# obd_schematic_27th_Jan_2026.net
KiCad netlist of a schematic drawn in EasyEDA Pro
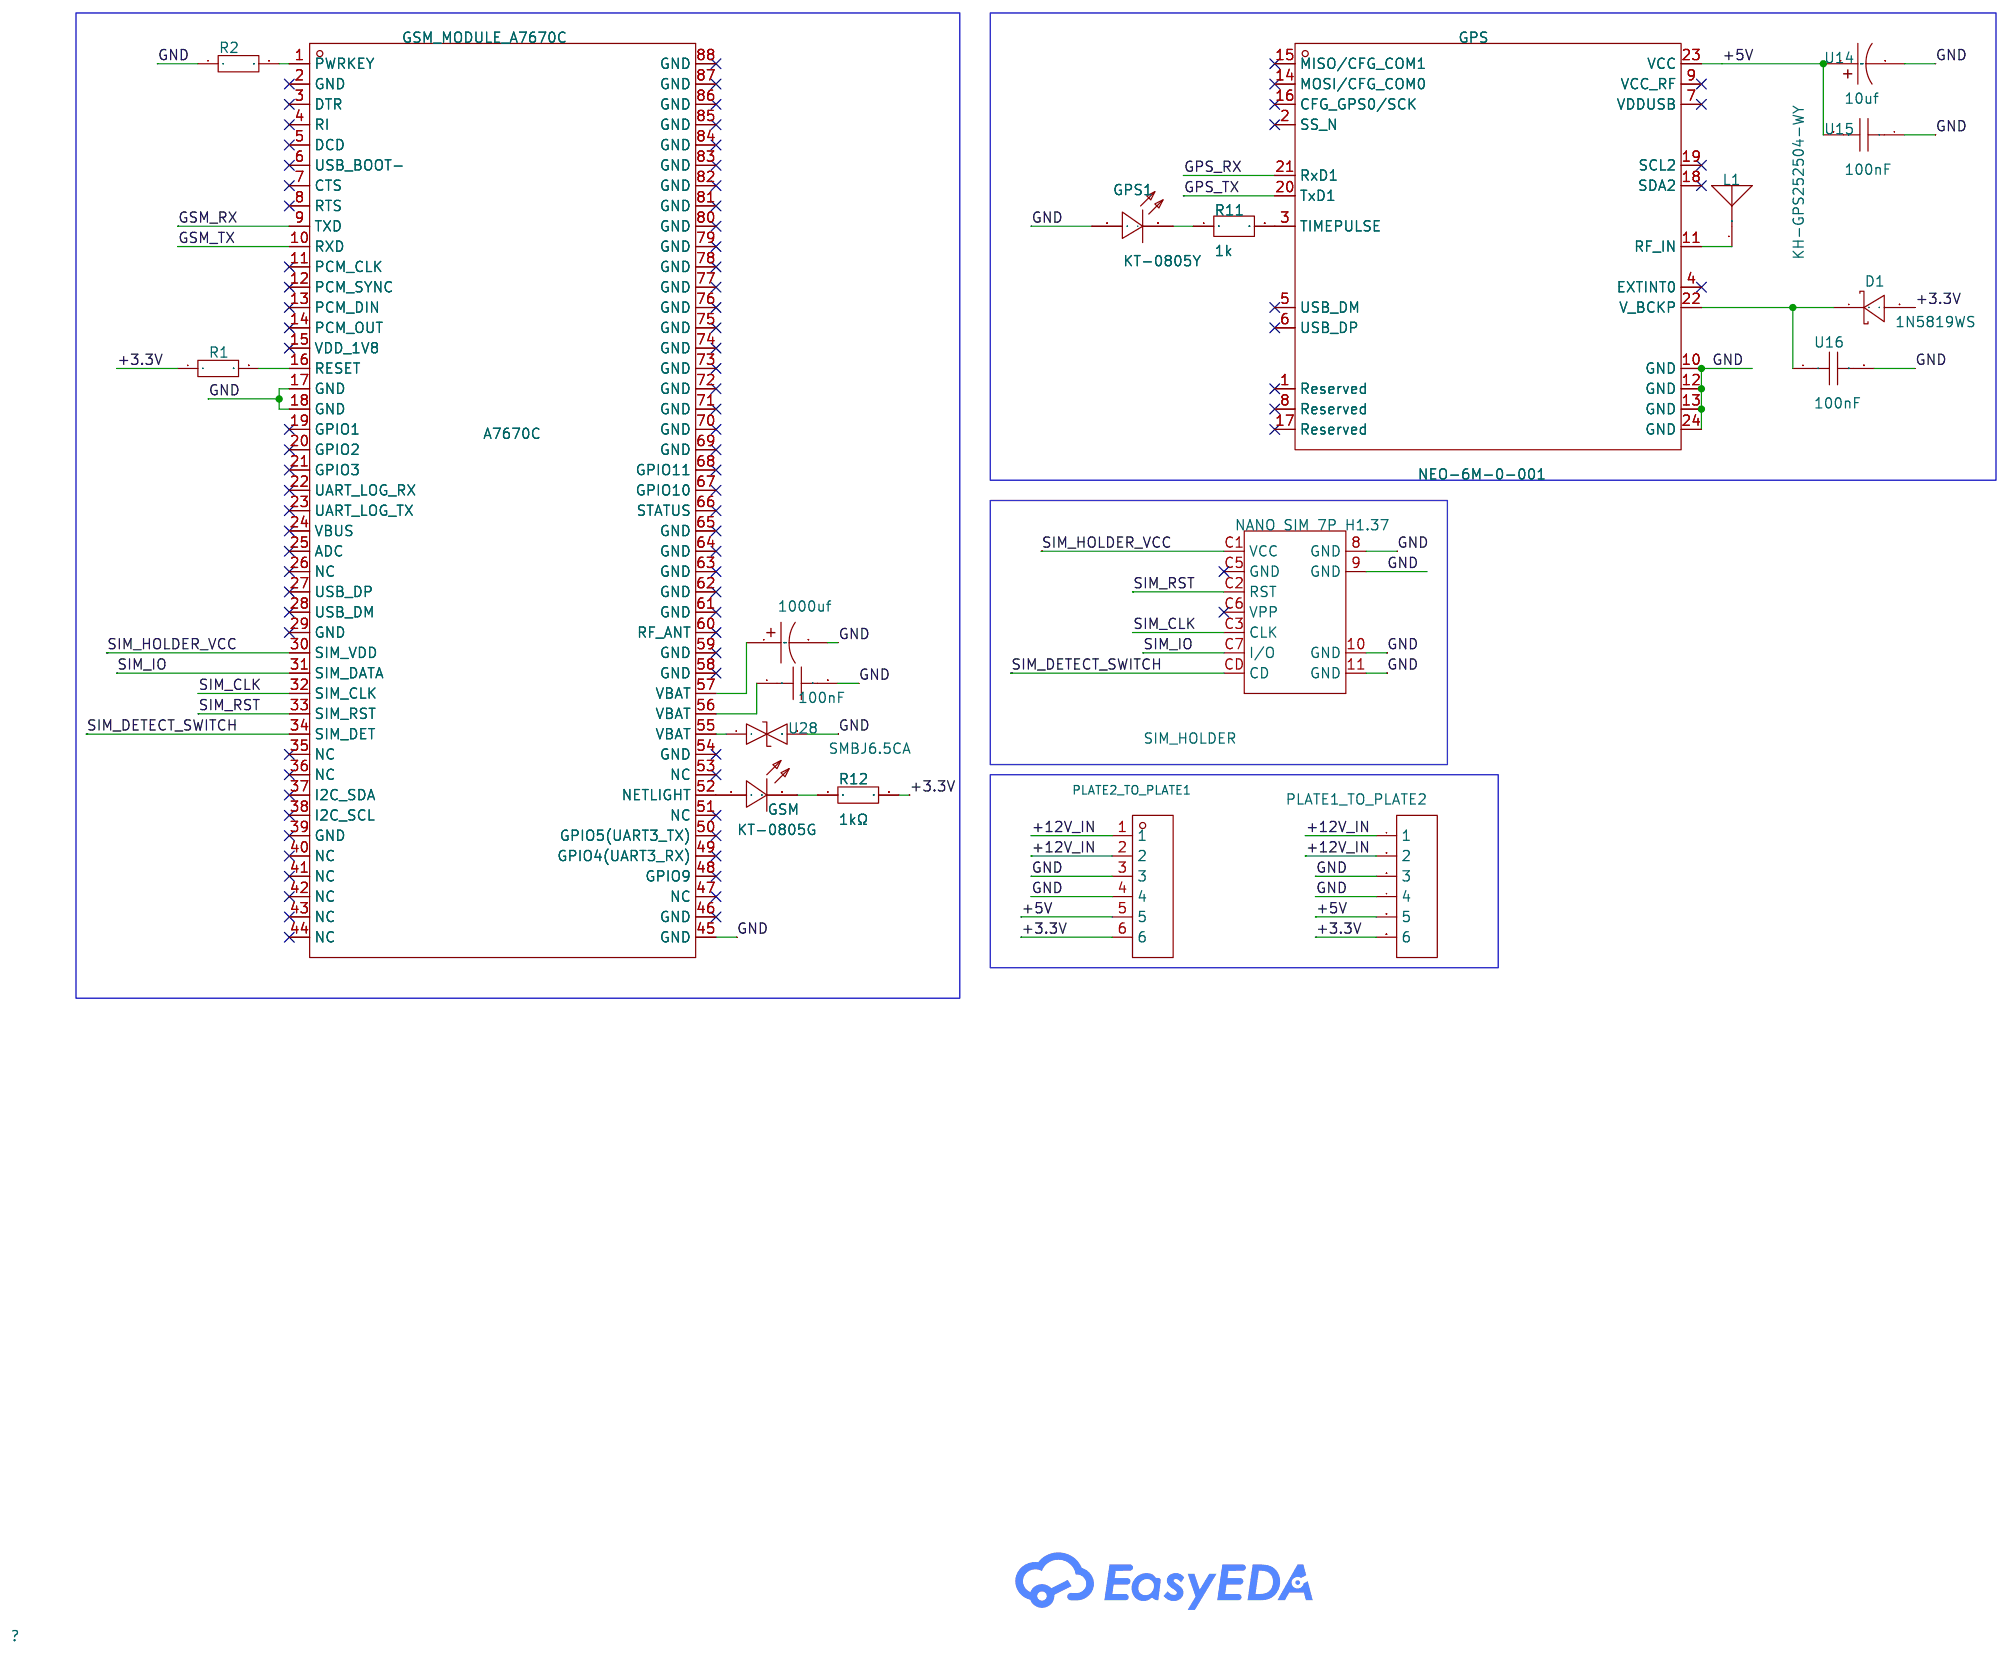
[diagram p0: gps_gsm]
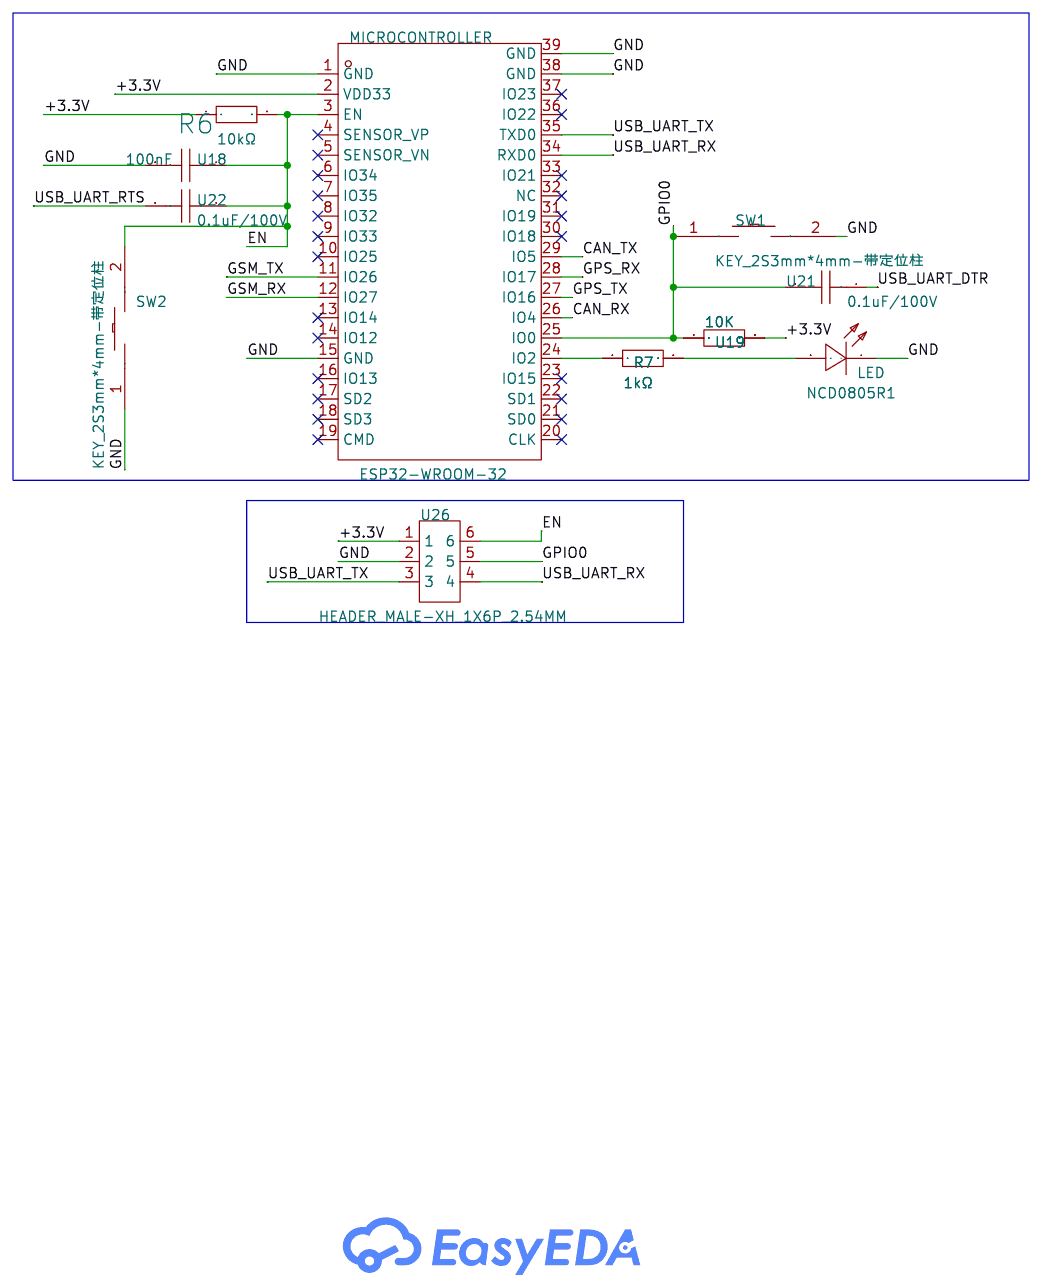
[diagram p1: Microcontroller]
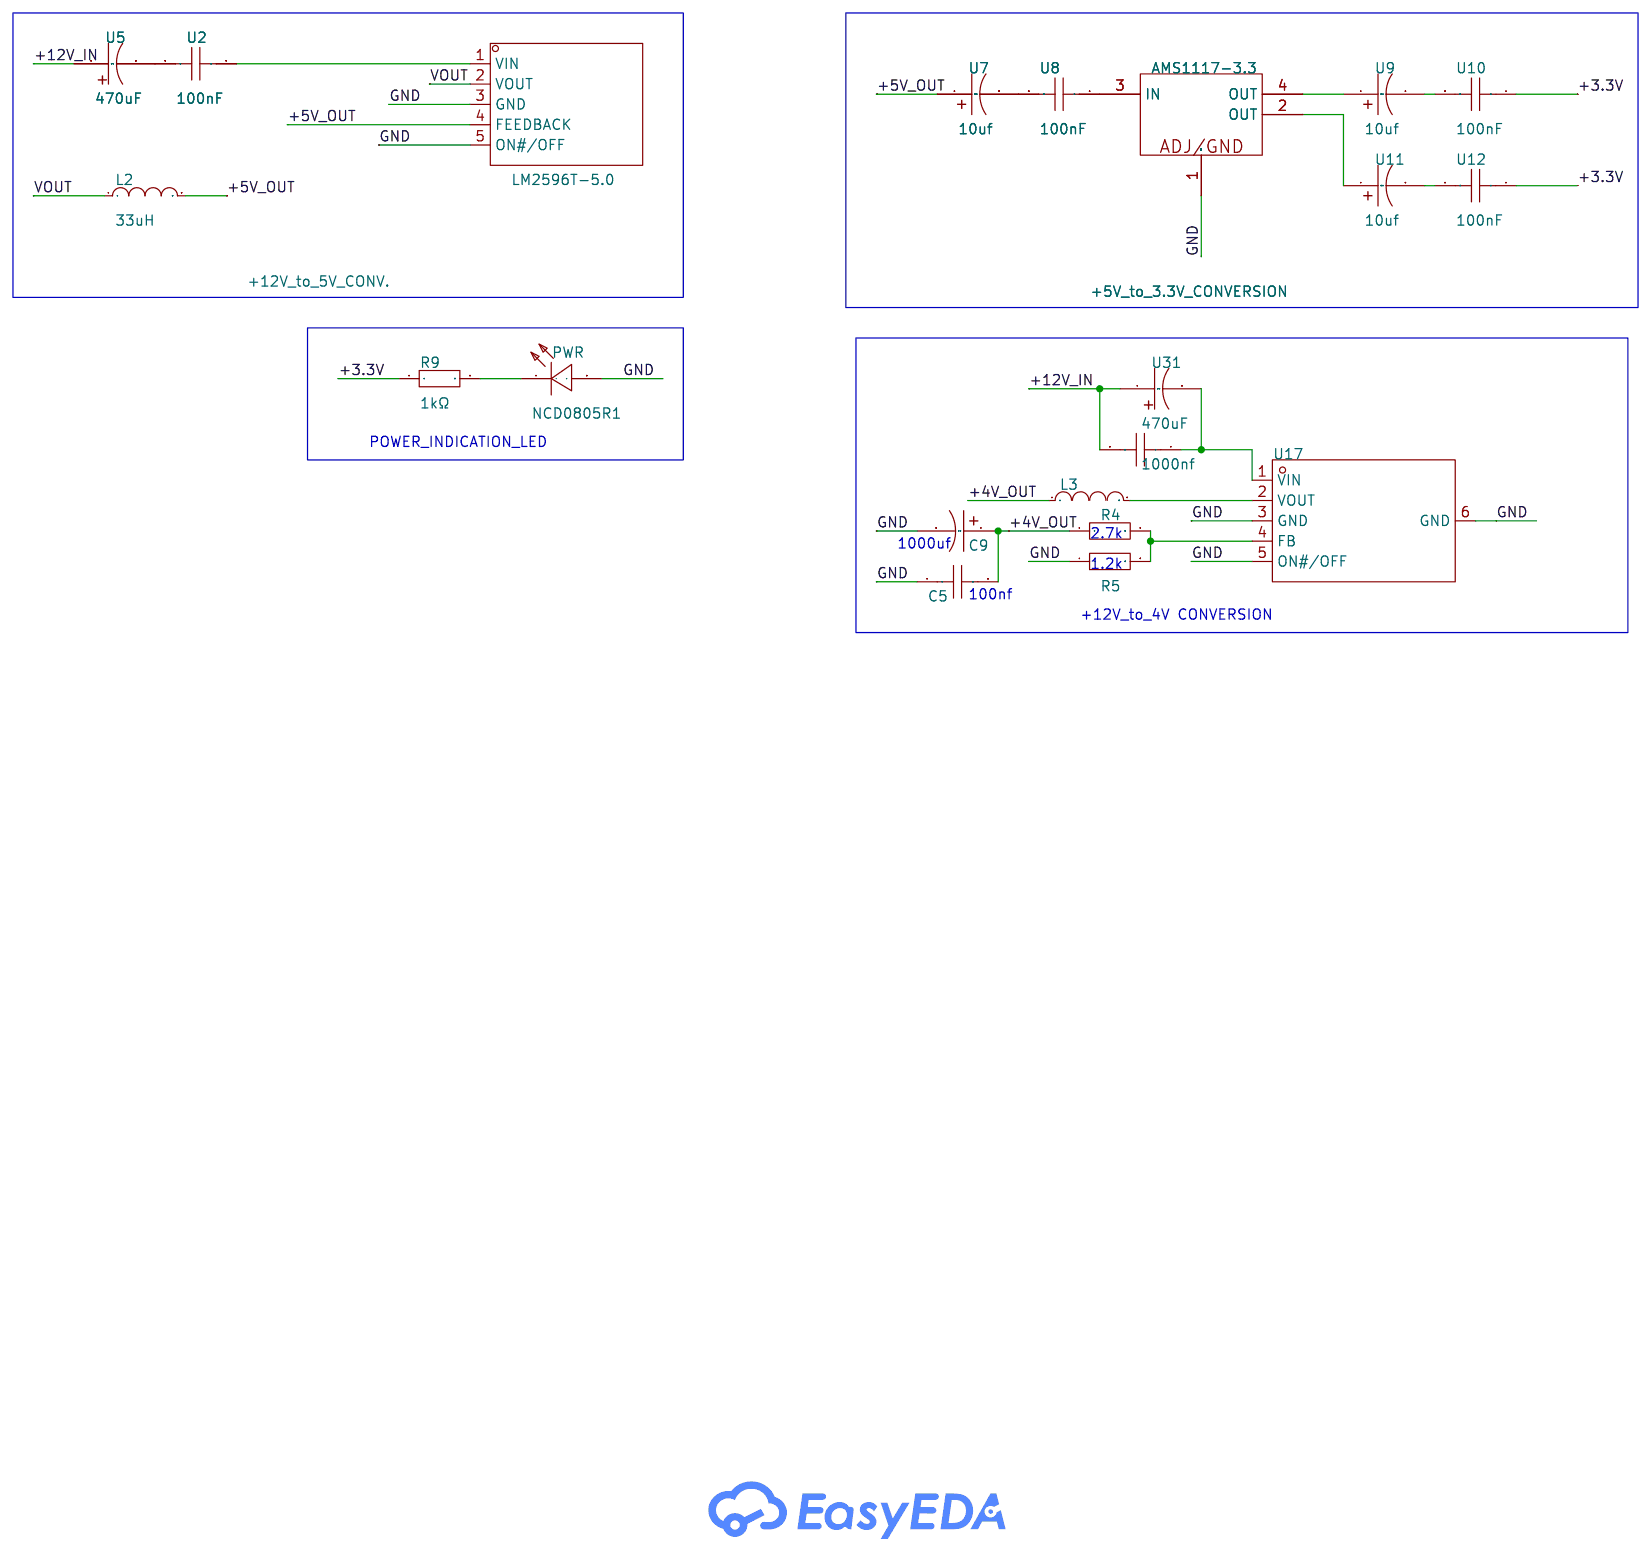
[diagram p2: power_supply]
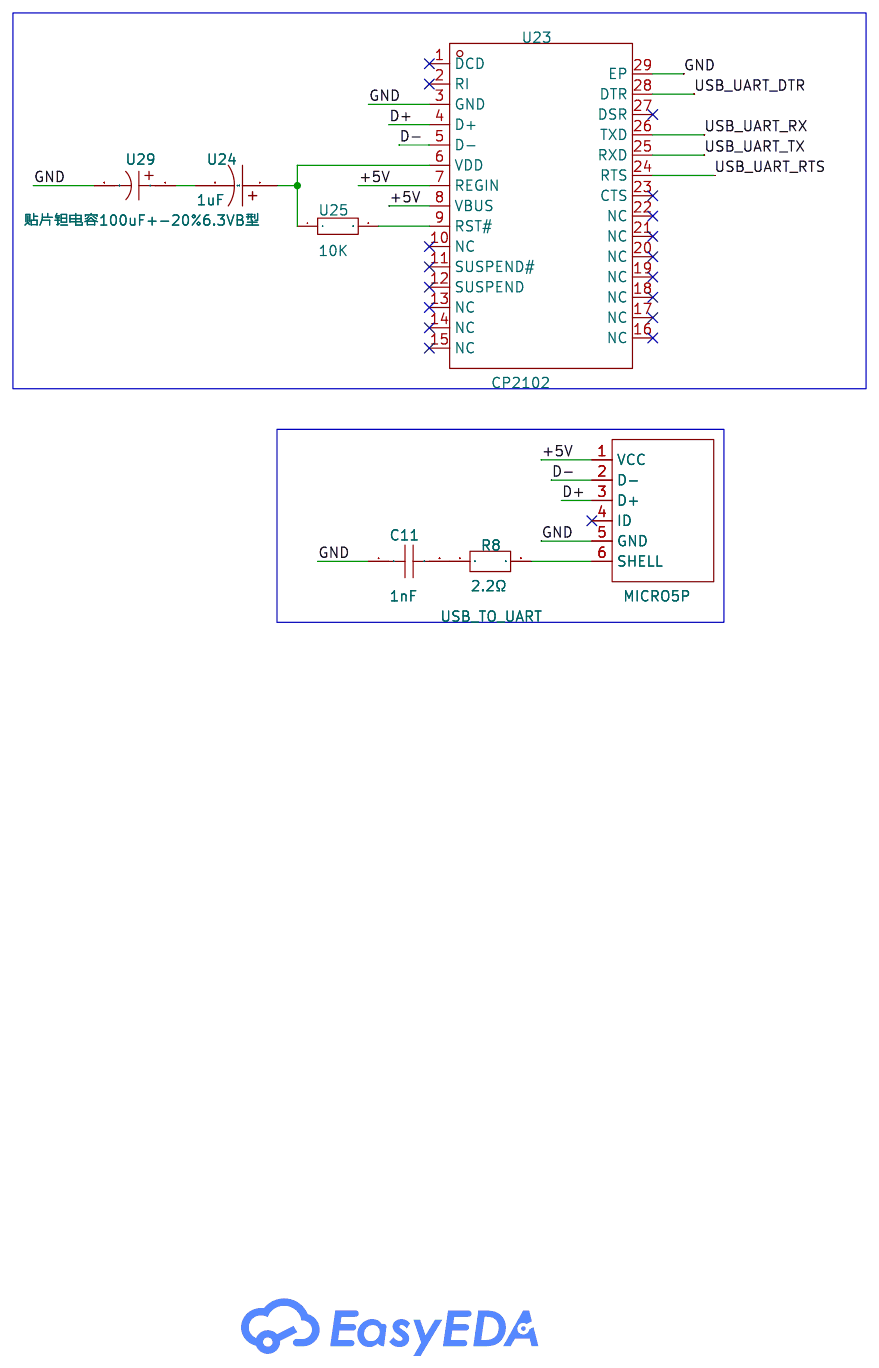
[diagram p3: usb_to_uart]
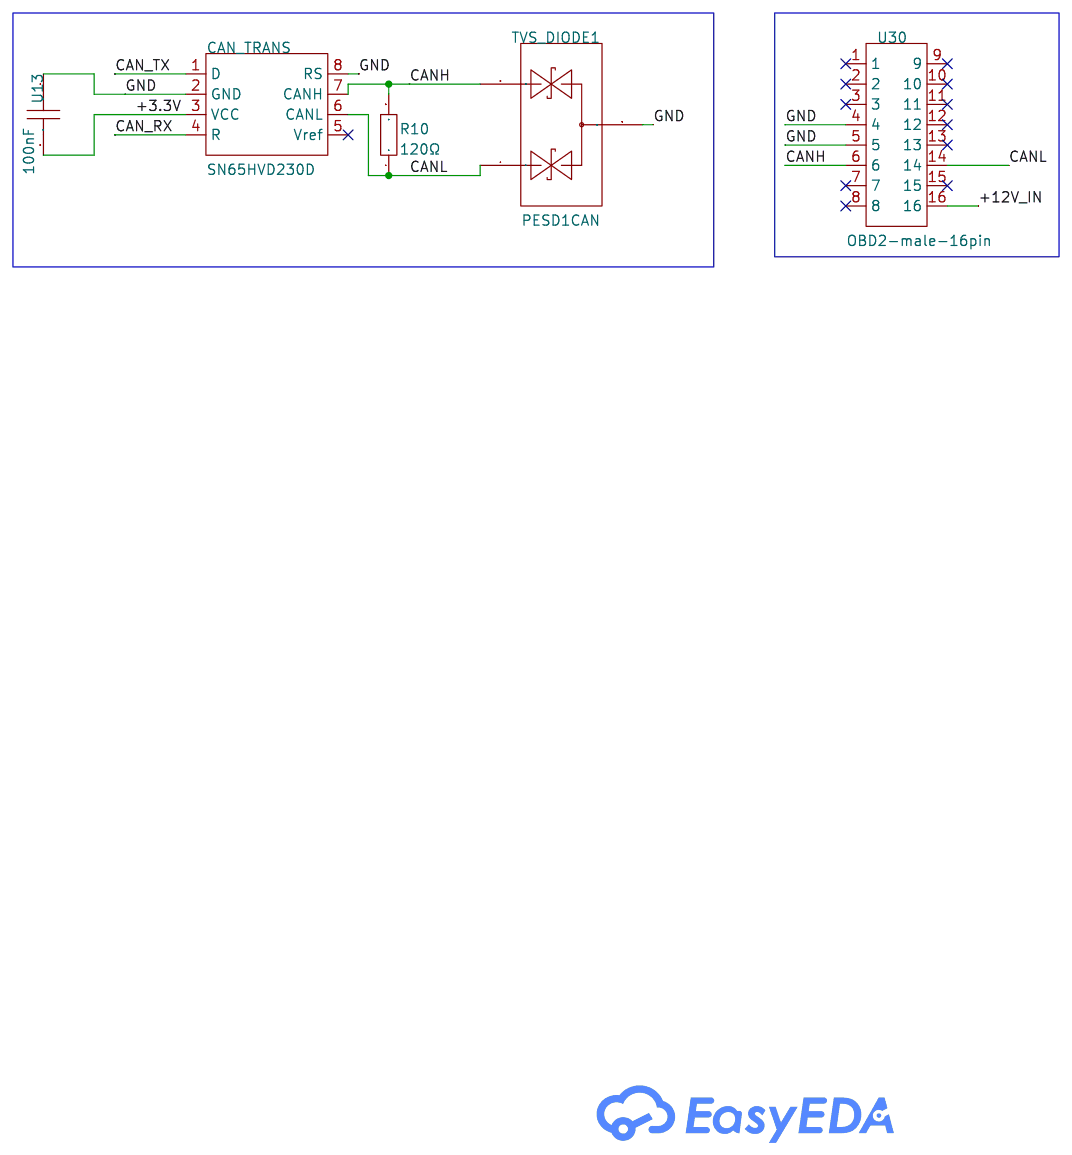
[diagram p4: can_obd_male_connector]

(export (version "E")
  (design (tool "Eeschema 10.0.6"))
  (components
    (comp (ref "100nF")
      (value "100nF")
      (footprint "easyedapro:CAP-TH_L18.0-W6.0-P15.00-D1.2")
      (fields
        (field (name "Manufacturer Part") "SMQP104K275XXD2B1515")
        (field (name "Manufacturer") "CHAMPION(全鹏)")
      )
      (libsource (lib "easyedapro") (part "SMQP104K275XXD2B1515"))
    )
    (comp (ref "1000uf")
      (value "1000uF")
      (footprint "easyedapro:CAP-TH_BD6.3-P2.50-D1.0-FD")
      (fields
        (field (name "Manufacturer Part") "SHW1000UF6.3V6.3X11")
        (field (name "Manufacturer") "KNSCHA(科尼盛)")
      )
      (libsource (lib "easyedapro") (part "SHW1000UF6.3V6.3X11"))
    )
    (comp (ref "D1")
      (value "1N5819WS")
      (footprint "easyedapro:SOD-323_L1.8-W1.3-LS2.5-RD")
      (fields (field (name "Manufacturer") "Hottech(合科泰)"))
      (libsource (lib "easyedapro") (part "1N5819WS"))
    )
    (comp (ref "GPS")
      (value "NEO-6M-0-001")
      (footprint "easyedapro:GPSM-SMD_24P-L16.0-W12.2-P1.10")
      (libsource (lib "easyedapro") (part "NEO-6M-0-001"))
    )
    (comp (ref "GPS1")
      (value "KT-0805Y")
      (footprint "easyedapro:LED0805-R-RD")
      (fields (field (name "Manufacturer") "KENTO"))
      (libsource (lib "easyedapro") (part "17-21SUYC/TR8"))
    )
    (comp (ref "GSM")
      (value "KT-0805G")
      (footprint "easyedapro:LED0805-R-RD")
      (fields (field (name "Manufacturer") "KENTO"))
      (libsource (lib "easyedapro") (part "0805G (Green)"))
    )
    (comp (ref "GSM_MODULE_A7670C")
      (value "A7670C")
      (footprint "easyedapro:WIRELM-SMD-88_L24.0-W24.0-P1.00-BL")
      (libsource (lib "easyedapro") (part "A7670C"))
    )
    (comp (ref "L1")
      (value "KH-GPS252504-WY")
      (footprint "easyedapro:ANT-TH_KH-GPS252504-WY")
      (fields (field (name "Manufacturer") "kinghelm(金航标)"))
      (libsource (lib "easyedapro") (part "KH-GPS252504-WY"))
    )
    (comp (ref "PLATE1_TO_PLATE2")
      (value "~")
      (footprint "easyedapro:HDR-TH_6P-P2.54-V-M-1")
      (libsource (lib "easyedapro") (part "Header-Male-2.54_1x6"))
    )
    (comp (ref "PLATE2_TO_PLATE1")
      (value "~")
      (footprint "easyedapro:HDR-TH_6P-P2.54-V-F")
      (libsource (lib "easyedapro") (part "Header-Female-2.54_1x6"))
    )
    (comp (ref "R1")
      (value "10kΩ")
      (footprint "easyedapro:R0805")
      (fields
        (field (name "Manufacturer Part") "RMCF0805FT10K0")
        (field (name "Manufacturer") "SEI(Stackpole Electronics Inc.)")
      )
      (libsource (lib "easyedapro") (part "RMCF0805FT10K0"))
    )
    (comp (ref "R2")
      (value "10kΩ")
      (footprint "easyedapro:R0805")
      (fields
        (field (name "Manufacturer Part") "RMCF0805FT10K0")
        (field (name "Manufacturer") "SEI(Stackpole Electronics Inc.)")
      )
      (libsource (lib "easyedapro") (part "RMCF0805FT10K0"))
    )
    (comp (ref "R11") (value "1k") (footprint "easyedapro:R0603") (libsource (lib "easyedapro") (part "1K")))
    (comp (ref "R12")
      (value "1kΩ")
      (footprint "easyedapro:R0805")
      (fields
        (field (name "Manufacturer Part") "0805W8F1001T5E")
        (field (name "Manufacturer") "UNI-ROYAL(厚声)")
      )
      (libsource (lib "easyedapro") (part "0805W8F1001T5E"))
    )
    (comp (ref "SIM_HOLDER")
      (value "NANO SIM 7P H1.37")
      (footprint "easyedapro:SIM-SMD_NANO-SIM-7P-H1.37")
      (fields (field (name "Manufacturer") "SHOU HAN(首韩)"))
      (libsource (lib "easyedapro") (part "NANO SIM 7P H1.37"))
    )
    (comp (ref "U14")
      (value "10uf")
      (footprint "easyedapro:CAP-SMD_L2.0-W1.3-FD")
      (libsource (lib "easyedapro") (part "10UF_C9900016685"))
    )
    (comp (ref "U15")
      (value "100nF")
      (footprint "easyedapro:CAP-TH_L5.0-W2.5-P5.00-D1.0")
      (libsource (lib "easyedapro") (part "100NF_C9900015256"))
    )
    (comp (ref "U16")
      (value "100nF")
      (footprint "easyedapro:CAP-TH_L5.0-W2.5-P5.00-D1.0")
      (libsource (lib "easyedapro") (part "100NF_C9900015256"))
    )
    (comp (ref "U28")
      (value "SMBJ6.5CA")
      (footprint "easyedapro:SMB_L4.6-W3.5-LS5.3-BI")
      (fields (field (name "Manufacturer") "R+O(宏嘉诚)"))
      (libsource (lib "easyedapro") (part "SMBJ6.5CA_C7420377"))
    )
    (comp (ref "LED")
      (value "NCD0805R1")
      (footprint "easyedapro:LED0805-RD")
      (fields (field (name "Manufacturer") "国星光电"))
      (libsource (lib "easyedapro") (part "FC-2012HRK-620D"))
    )
    (comp (ref "MICROCONTROLLER")
      (value "ESP32-WROOM-32")
      (footprint "easyedapro:WIFIM-SMD_39P-L25.5-W18.0-P1.27")
      (libsource (lib "easyedapro") (part "ESP32-WROOM-32_C503587"))
    )
    (comp (ref "R6")
      (value "10kΩ")
      (footprint "easyedapro:R0603")
      (fields
        (field (name "Manufacturer Part") "0603WAF1002T5E")
        (field (name "Manufacturer") "UNI-ROYAL(厚声)")
      )
      (libsource (lib "easyedapro") (part "0603WAF1002T5E"))
    )
    (comp (ref "R7")
      (value "1kΩ")
      (footprint "easyedapro:R0805")
      (fields
        (field (name "Manufacturer Part") "0805W8F1001T5E")
        (field (name "Manufacturer") "UNI-ROYAL(厚声)")
      )
      (libsource (lib "easyedapro") (part "0805W8F1001T5E"))
    )
    (comp (ref "SW1")
      (value "KEY_2S3mm*4mm-带定位柱")
      (footprint "easyedapro:KEY-SMD_L4.0-W3.7-LS4.8")
      (libsource (lib "easyedapro") (part "KEY_2S3MM*4MM-带定位柱"))
    )
    (comp (ref "SW2")
      (value "KEY_2S3mm*4mm-带定位柱")
      (footprint "easyedapro:KEY-SMD_L4.0-W3.7-LS4.8")
      (libsource (lib "easyedapro") (part "KEY_2S3MM*4MM-带定位柱"))
    )
    (comp (ref "U18")
      (value "100nF")
      (footprint "easyedapro:CAP-TH_L5.0-W2.5-P5.00-D1.0")
      (libsource (lib "easyedapro") (part "100NF_C9900015256"))
    )
    (comp (ref "U19")
      (value "10K")
      (footprint "easyedapro:R0805")
      (libsource (lib "easyedapro") (part "10K"))
    )
    (comp (ref "U21")
      (value "0.1uF/100V")
      (footprint "easyedapro:C0805")
      (libsource (lib "easyedapro") (part "0.1UF/100V"))
    )
    (comp (ref "U22")
      (value "0.1uF/100V")
      (footprint "easyedapro:C0805")
      (libsource (lib "easyedapro") (part "0.1UF/100V"))
    )
    (comp (ref "U26")
      (value "HEADER_MALE-XH_1X6P_2.54MM")
      (footprint "easyedapro:CONN-TH_6P-P2.50-V-M_HEADER-MALE")
      (libsource (lib "easyedapro") (part "HEADER_MALE-XH_1X6P_2.54MM"))
    )
    (comp (ref "+5V_to_3.3V_CONVERSION")
      (value "AMS1117-3.3")
      (footprint "easyedapro:SOT-223-3_L6.4-W3.5-P2.30-LS7.0-BR")
      (fields (field (name "Manufacturer") "国芯佳品"))
      (libsource (lib "easyedapro") (part "AMS1117-3.3_C2992570"))
    )
    (comp (ref "+12V_to_5V_CONV.")
      (value "LM2596T-5.0")
      (footprint "easyedapro:TO-220-5L_L10.2-W4.5-P1.71-L")
      (libsource (lib "easyedapro") (part "LM2596-5V"))
    )
    (comp (ref "1000nf")
      (value "100nF")
      (footprint "easyedapro:CAP-TH_L7.3-W3.2-P5.00-D0.5")
      (fields
        (field (name "Manufacturer Part") "MMTSA0050J10400000200")
        (field (name "Manufacturer") "NISSEI(日精)")
      )
      (libsource (lib "easyedapro") (part "MMTSA0050J10400000200"))
    )
    (comp (ref "C5")
      (value "100nF")
      (footprint "easyedapro:CAP-TH_L18.0-W6.0-P15.00-D1.2")
      (fields
        (field (name "Manufacturer Part") "SMQP104K275XXD2B1515")
        (field (name "Manufacturer") "CHAMPION(全鹏)")
      )
      (libsource (lib "easyedapro") (part "SMQP104K275XXD2B1515"))
    )
    (comp (ref "C9")
      (value "1000uF")
      (footprint "easyedapro:CAP-TH_BD6.3-P2.50-D1.0-FD")
      (fields
        (field (name "Manufacturer Part") "SHW1000UF6.3V6.3X11")
        (field (name "Manufacturer") "KNSCHA(科尼盛)")
      )
      (libsource (lib "easyedapro") (part "SHW1000UF6.3V6.3X11"))
    )
    (comp (ref "L2")
      (value "33uH")
      (footprint "easyedapro:IND-SMD_L7.0-W6.6_FXL0630")
      (libsource (lib "easyedapro") (part "33UH_C9900023951"))
    )
    (comp (ref "L3")
      (value "33uH")
      (footprint "easyedapro:IND-SMD_L6.0-W6.0")
      (fields (field (name "Manufacturer Part") "CKCS6045-33uH/M") (field (name "Manufacturer") "CENKER(岑科)"))
      (libsource (lib "easyedapro") (part "CKCS6045-33UH/M"))
    )
    (comp (ref "PWR")
      (value "NCD0805R1")
      (footprint "easyedapro:LED0805-RD")
      (fields (field (name "Manufacturer") "国星光电"))
      (libsource (lib "easyedapro") (part "FC-2012HRK-620D"))
    )
    (comp (ref "R4")
      (value "2.7kΩ")
      (footprint "easyedapro:R0603")
      (fields (field (name "Manufacturer Part") "RC0603JR-072K7L") (field (name "Manufacturer") "YAGEO(国巨)"))
      (libsource (lib "easyedapro") (part "RC0603JR-072K7L"))
    )
    (comp (ref "R5")
      (value "1.2kΩ")
      (footprint "easyedapro:R0805")
      (fields (field (name "Manufacturer Part") "RC0805FR-071K2L") (field (name "Manufacturer") "YAGEO(国巨)"))
      (libsource (lib "easyedapro") (part "RC0805FR-071K2L"))
    )
    (comp (ref "R9")
      (value "1kΩ")
      (footprint "easyedapro:R0805")
      (fields
        (field (name "Manufacturer Part") "0805W8F1001T5E")
        (field (name "Manufacturer") "UNI-ROYAL(厚声)")
      )
      (libsource (lib "easyedapro") (part "0805W8F1001T5E"))
    )
    (comp (ref "U2")
      (value "100nF")
      (footprint "easyedapro:CAP-TH_L5.0-W2.5-P5.00-D1.0")
      (libsource (lib "easyedapro") (part "100NF_C9900015256"))
    )
    (comp (ref "U5")
      (value "470uF")
      (footprint "easyedapro:CAP-SMD_BD10.0-L10.3-W10.3-LS11.0-FD-1")
      (libsource (lib "easyedapro") (part "470UF"))
    )
    (comp (ref "U7")
      (value "10uf")
      (footprint "easyedapro:CAP-SMD_L2.0-W1.3-FD")
      (libsource (lib "easyedapro") (part "10UF_C9900016685"))
    )
    (comp (ref "U8")
      (value "100nF")
      (footprint "easyedapro:CAP-TH_L5.0-W2.5-P5.00-D1.0")
      (libsource (lib "easyedapro") (part "100NF_C9900015256"))
    )
    (comp (ref "U9")
      (value "10uf")
      (footprint "easyedapro:CAP-SMD_L2.0-W1.3-FD")
      (libsource (lib "easyedapro") (part "10UF_C9900016685"))
    )
    (comp (ref "U10")
      (value "100nF")
      (footprint "easyedapro:CAP-TH_L5.0-W2.5-P5.00-D1.0")
      (libsource (lib "easyedapro") (part "100NF_C9900015256"))
    )
    (comp (ref "U11")
      (value "10uf")
      (footprint "easyedapro:CAP-SMD_L2.0-W1.3-FD")
      (libsource (lib "easyedapro") (part "10UF_C9900016685"))
    )
    (comp (ref "U12")
      (value "100nF")
      (footprint "easyedapro:CAP-TH_L5.0-W2.5-P5.00-D1.0")
      (libsource (lib "easyedapro") (part "100NF_C9900015256"))
    )
    (comp (ref "U17")
      (value "~")
      (footprint "easyedapro:TO-263-5_L10.2-W8.6-P1.70-LS14.4-TL")
      (fields (field (name "Manufacturer Part") "LM2596S-ADJ/TR") (field (name "Manufacturer") "HGC(华冠)"))
      (libsource (lib "easyedapro") (part "LM2596S-ADJ/TR_C508707"))
    )
    (comp (ref "U31")
      (value "470uF")
      (footprint "easyedapro:CAP-SMD_BD10.0-L10.3-W10.3-LS11.0-FD-1")
      (libsource (lib "easyedapro") (part "470UF"))
    )
    (comp (ref "C11")
      (value "1nF")
      (footprint "easyedapro:C0805")
      (description "Capacitance:1000pF Tolerance:±20% Tolerance:±20% Voltage Rating:100V Temperature Coefficient:X7R")
      (fields (field (name "Manufacturer Part") "C2012X7R2A102M/10") (field (name "Manufacturer") "TDK"))
      (libsource (lib "easyedapro") (part "C2012X7R2A102M/10"))
    )
    (comp (ref "R8")
      (value "2.2Ω")
      (footprint "easyedapro:RES-TH_L48.0-W10.0-P51.00-D0.8")
      (description "Type:Ceramic resistor Resistance:2.2Ω Power(Watts):10W")
      (fields
        (field (name "Manufacturer Part") "CERAMIC RESISTOR 10W/ 2,2 OHM")
        (field (name "Manufacturer") "Visaton")
      )
      (libsource (lib "easyedapro") (part "CERAMIC RESISTOR 10W/ 2,2 OHM"))
    )
    (comp (ref "U23")
      (value "CP2102")
      (footprint "easyedapro:QFN-28_L5.0-W5.0-P0.50-TL-EP3.2")
      (libsource (lib "easyedapro") (part "CP2102"))
    )
    (comp (ref "U24")
      (value "1uF")
      (footprint "easyedapro:CAP-SMD_L3.5-W2.8-FD")
      (fields (field (name "Manufacturer Part") "CA45-B-35V-1uF-K") (field (name "Manufacturer") "TORCH(火炬)"))
      (libsource (lib "easyedapro") (part "CA45-B-35V-1μF-K"))
    )
    (comp (ref "U25")
      (value "10K")
      (footprint "easyedapro:R0805")
      (libsource (lib "easyedapro") (part "10K"))
    )
    (comp (ref "U29")
      (value "贴片钽电容100uF+-20%6.3VB型")
      (footprint "easyedapro:CAP-SMD_L3.5-W2.8-FD")
      (libsource (lib "easyedapro") (part "贴片钽电容100UF+-20%6.3VB型"))
    )
    (comp (ref "USB_TO_UART")
      (value "MICRO5P")
      (footprint "easyedapro:MICRO-USB-SMD_MICRO-21-P2-T3")
      (libsource (lib "easyedapro") (part "MICRO5P"))
    )
    (comp (ref "CAN_TRANS")
      (value "SN65HVD230D")
      (footprint "easyedapro:SOIC-8_L4.9-W3.9-P1.27-LS6.0-BL")
      (fields (field (name "Manufacturer") "TI(德州仪器)"))
      (libsource (lib "easyedapro") (part "SN65HVD230D"))
    )
    (comp (ref "R10")
      (value "120Ω")
      (footprint "easyedapro:R1206")
      (fields
        (field (name "Manufacturer Part") "1206W4F1200T5E")
        (field (name "Manufacturer") "UNI-ROYAL(厚声)")
      )
      (libsource (lib "easyedapro") (part "1206W4F1200T5E_C17909"))
    )
    (comp (ref "TVS_DIODE1")
      (value "PESD1CAN")
      (footprint "easyedapro:SOT-23_L2.9-W1.3-P1.90-LS2.4-BR")
      (libsource (lib "easyedapro") (part "PESD1CAN"))
    )
    (comp (ref "U13")
      (value "100nF")
      (footprint "easyedapro:CAP-TH_L5.0-W2.5-P5.00-D1.0")
      (libsource (lib "easyedapro") (part "100NF_C9900015256"))
    )
    (comp (ref "U30")
      (value "OBD2-male-16pin")
      (footprint "easyedapro:CONN-TH_OBD2")
      (libsource (lib "easyedapro") (part "OBD2-MALE-16PIN"))
    )
  )
  (nets
    (net (code "1") (name "+3.3V") (class "Default")
      (node (ref "CAN_TRANS") (pin "3") (pinfunction "VCC_3") (pintype "unspecified"))
      (node (ref "D1") (pin "2") (pinfunction "A_2") (pintype "unspecified"))
      (node (ref "MICROCONTROLLER") (pin "2") (pinfunction "VDD33_2") (pintype "unspecified"))
      (node (ref "PLATE1_TO_PLATE2") (pin "6") (pinfunction "6_6") (pintype "input"))
      (node (ref "PLATE2_TO_PLATE1") (pin "6") (pinfunction "6_6") (pintype "input"))
      (node (ref "R1") (pin "1") (pinfunction "1_1") (pintype "input"))
      (node (ref "R12") (pin "2") (pinfunction "2_2") (pintype "input"))
      (node (ref "R6") (pin "1") (pinfunction "1_1") (pintype "input"))
      (node (ref "R9") (pin "1") (pinfunction "1_1") (pintype "input"))
      (node (ref "U10") (pin "1") (pinfunction "1_1") (pintype "unspecified"))
      (node (ref "U12") (pin "1") (pinfunction "1_1") (pintype "unspecified"))
      (node (ref "U13") (pin "2") (pinfunction "2_2") (pintype "unspecified"))
      (node (ref "U19") (pin "2") (pinfunction "2_2") (pintype "unspecified"))
      (node (ref "U26") (pin "1") (pinfunction "1_1") (pintype "unspecified"))
    )
    (net (code "2") (name "+4V_OUT") (class "Default")
      (node (ref "C5") (pin "2") (pinfunction "2_2") (pintype "input"))
      (node (ref "C9") (pin "1") (pinfunction "1_1") (pintype "input"))
      (node (ref "L3") (pin "1") (pinfunction "1_1") (pintype "input"))
      (node (ref "R4") (pin "1") (pinfunction "1_1") (pintype "input"))
    )
    (net (code "3") (name "+5V") (class "Default")
      (node (ref "GPS") (pin "23") (pinfunction "VCC_23") (pintype "unspecified"))
      (node (ref "PLATE1_TO_PLATE2") (pin "5") (pinfunction "5_5") (pintype "input"))
      (node (ref "PLATE2_TO_PLATE1") (pin "5") (pinfunction "5_5") (pintype "input"))
      (node (ref "U14") (pin "1") (pinfunction "1_1") (pintype "unspecified"))
      (node (ref "U15") (pin "2") (pinfunction "2_2") (pintype "unspecified"))
      (node (ref "U23") (pin "7") (pinfunction "REGIN_7") (pintype "unspecified"))
      (node (ref "U23") (pin "8") (pinfunction "VBUS_8") (pintype "unspecified"))
      (node (ref "USB_TO_UART") (pin "1") (pinfunction "VCC_1") (pintype "unspecified"))
    )
    (net (code "4") (name "+5V_OUT") (class "Default")
      (node (ref "+12V_to_5V_CONV.") (pin "4") (pinfunction "FEEDBACK_4") (pintype "unspecified"))
      (node (ref "L2") (pin "2") (pinfunction "2_2") (pintype "unspecified"))
      (node (ref "U7") (pin "1") (pinfunction "1_1") (pintype "unspecified"))
    )
    (net (code "5") (name "+12V_IN") (class "Default")
      (node (ref "1000nf") (pin "2") (pinfunction "2_2") (pintype "input"))
      (node (ref "PLATE1_TO_PLATE2") (pin "1") (pinfunction "1_1") (pintype "input"))
      (node (ref "PLATE1_TO_PLATE2") (pin "2") (pinfunction "2_2") (pintype "input"))
      (node (ref "PLATE2_TO_PLATE1") (pin "1") (pinfunction "1_1") (pintype "input"))
      (node (ref "PLATE2_TO_PLATE1") (pin "2") (pinfunction "2_2") (pintype "input"))
      (node (ref "U30") (pin "16") (pinfunction "16_16") (pintype "unspecified"))
      (node (ref "U31") (pin "1") (pinfunction "1_1") (pintype "unspecified"))
      (node (ref "U5") (pin "1") (pinfunction "1_1") (pintype "unspecified"))
    )
    (net (code "6") (name "CANH") (class "Default")
      (node (ref "CAN_TRANS") (pin "7") (pinfunction "CANH_7") (pintype "unspecified"))
      (node (ref "R10") (pin "2") (pinfunction "2_2") (pintype "input"))
      (node (ref "TVS_DIODE1") (pin "2") (pinfunction "2_2") (pintype "unspecified"))
      (node (ref "U30") (pin "6") (pinfunction "6_6") (pintype "unspecified"))
    )
    (net (code "7") (name "CANL") (class "Default")
      (node (ref "CAN_TRANS") (pin "6") (pinfunction "CANL_6") (pintype "unspecified"))
      (node (ref "R10") (pin "1") (pinfunction "1_1") (pintype "input"))
      (node (ref "TVS_DIODE1") (pin "1") (pinfunction "1_1") (pintype "unspecified"))
      (node (ref "U30") (pin "14") (pinfunction "14_14") (pintype "unspecified"))
    )
    (net (code "8") (name "CAN_RX") (class "Default")
      (node (ref "CAN_TRANS") (pin "4") (pinfunction "R_4") (pintype "unspecified"))
      (node (ref "MICROCONTROLLER") (pin "26") (pinfunction "IO4_26") (pintype "unspecified"))
    )
    (net (code "9") (name "CAN_TX") (class "Default")
      (node (ref "CAN_TRANS") (pin "1") (pinfunction "D_1") (pintype "unspecified"))
      (node (ref "MICROCONTROLLER") (pin "29") (pinfunction "IO5_29") (pintype "unspecified"))
    )
    (net (code "10") (name "D+") (class "Default")
      (node (ref "U23") (pin "4") (pinfunction "D+_4") (pintype "unspecified"))
      (node (ref "USB_TO_UART") (pin "3") (pinfunction "D+_3") (pintype "unspecified"))
    )
    (net (code "11") (name "D-") (class "Default")
      (node (ref "U23") (pin "5") (pinfunction "D-_5") (pintype "unspecified"))
      (node (ref "USB_TO_UART") (pin "2") (pinfunction "D-_2") (pintype "unspecified"))
    )
    (net (code "12") (name "EN") (class "Default")
      (node (ref "MICROCONTROLLER") (pin "3") (pinfunction "EN_3") (pintype "unspecified"))
      (node (ref "R6") (pin "2") (pinfunction "2_2") (pintype "input"))
      (node (ref "SW2") (pin "2") (pinfunction "2_2") (pintype "unspecified"))
      (node (ref "U18") (pin "1") (pinfunction "1_1") (pintype "unspecified"))
      (node (ref "U22") (pin "1") (pinfunction "1_1") (pintype "unspecified"))
      (node (ref "U26") (pin "6") (pinfunction "6_6") (pintype "unspecified"))
    )
    (net (code "13") (name "GND") (class "Default")
      (node (ref "+12V_to_5V_CONV.") (pin "3") (pinfunction "GND_3") (pintype "unspecified"))
      (node (ref "+12V_to_5V_CONV.") (pin "5") (pinfunction "ON#/OFF_5") (pintype "unspecified"))
      (node (ref "+5V_to_3.3V_CONVERSION") (pin "1") (pinfunction "ADJ/GND_1") (pintype "unspecified"))
      (node (ref "1000uf") (pin "2") (pinfunction "2_2") (pintype "input"))
      (node (ref "100nF") (pin "2") (pinfunction "2_2") (pintype "input"))
      (node (ref "C11") (pin "1") (pinfunction "1_1") (pintype "unspecified"))
      (node (ref "C5") (pin "1") (pinfunction "1_1") (pintype "input"))
      (node (ref "C9") (pin "2") (pinfunction "2_2") (pintype "input"))
      (node (ref "CAN_TRANS") (pin "2") (pinfunction "GND_2") (pintype "unspecified"))
      (node (ref "CAN_TRANS") (pin "8") (pinfunction "RS_8") (pintype "unspecified"))
      (node (ref "GPS") (pin "10") (pinfunction "GND_10") (pintype "unspecified"))
      (node (ref "GPS") (pin "12") (pinfunction "GND_12") (pintype "unspecified"))
      (node (ref "GPS") (pin "13") (pinfunction "GND_13") (pintype "unspecified"))
      (node (ref "GPS") (pin "24") (pinfunction "GND_24") (pintype "unspecified"))
      (node (ref "GPS1") (pin "1") (pinfunction "+_1") (pintype "unspecified"))
      (node (ref "GSM_MODULE_A7670C") (pin "17") (pinfunction "GND_17") (pintype "input"))
      (node (ref "GSM_MODULE_A7670C") (pin "18") (pinfunction "GND_18") (pintype "input"))
      (node (ref "GSM_MODULE_A7670C") (pin "45") (pinfunction "GND_45") (pintype "input"))
      (node (ref "LED") (pin "1") (pinfunction "-_1") (pintype "unspecified"))
      (node (ref "MICROCONTROLLER") (pin "1") (pinfunction "GND_1") (pintype "unspecified"))
      (node (ref "MICROCONTROLLER") (pin "15") (pinfunction "GND_15") (pintype "unspecified"))
      (node (ref "MICROCONTROLLER") (pin "38") (pinfunction "GND_38") (pintype "unspecified"))
      (node (ref "MICROCONTROLLER") (pin "39") (pinfunction "GND_39") (pintype "unspecified"))
      (node (ref "PLATE1_TO_PLATE2") (pin "3") (pinfunction "3_3") (pintype "input"))
      (node (ref "PLATE1_TO_PLATE2") (pin "4") (pinfunction "4_4") (pintype "input"))
      (node (ref "PLATE2_TO_PLATE1") (pin "3") (pinfunction "3_3") (pintype "input"))
      (node (ref "PLATE2_TO_PLATE1") (pin "4") (pinfunction "4_4") (pintype "input"))
      (node (ref "PWR") (pin "2") (pinfunction "+_2") (pintype "unspecified"))
      (node (ref "R2") (pin "1") (pinfunction "1_1") (pintype "input"))
      (node (ref "R5") (pin "1") (pinfunction "1_1") (pintype "input"))
      (node (ref "SIM_HOLDER") (pin "10") (pinfunction "GND_10") (pintype "unspecified"))
      (node (ref "SIM_HOLDER") (pin "11") (pinfunction "GND_11") (pintype "unspecified"))
      (node (ref "SIM_HOLDER") (pin "8") (pinfunction "GND_8") (pintype "unspecified"))
      (node (ref "SIM_HOLDER") (pin "9") (pinfunction "GND_9") (pintype "unspecified"))
      (node (ref "SW1") (pin "2") (pinfunction "2_2") (pintype "unspecified"))
      (node (ref "SW2") (pin "1") (pinfunction "1_1") (pintype "unspecified"))
      (node (ref "TVS_DIODE1") (pin "3") (pinfunction "3_3") (pintype "unspecified"))
      (node (ref "U13") (pin "1") (pinfunction "1_1") (pintype "unspecified"))
      (node (ref "U14") (pin "2") (pinfunction "2_2") (pintype "unspecified"))
      (node (ref "U15") (pin "1") (pinfunction "1_1") (pintype "unspecified"))
      (node (ref "U16") (pin "2") (pinfunction "2_2") (pintype "unspecified"))
      (node (ref "U17") (pin "3") (pinfunction "GND_3") (pintype "input"))
      (node (ref "U17") (pin "5") (pinfunction "ON#/OFF_5") (pintype "input"))
      (node (ref "U17") (pin "6") (pinfunction "GND_6") (pintype "input"))
      (node (ref "U18") (pin "2") (pinfunction "2_2") (pintype "unspecified"))
      (node (ref "U23") (pin "29") (pinfunction "EP_29") (pintype "unspecified"))
      (node (ref "U23") (pin "3") (pinfunction "GND_3") (pintype "unspecified"))
      (node (ref "U26") (pin "2") (pinfunction "2_2") (pintype "unspecified"))
      (node (ref "U28") (pin "2") (pinfunction "2_2") (pintype "unspecified"))
      (node (ref "U29") (pin "2") (pinfunction "2_2") (pintype "input"))
      (node (ref "U30") (pin "4") (pinfunction "4_4") (pintype "unspecified"))
      (node (ref "U30") (pin "5") (pinfunction "5_5") (pintype "unspecified"))
      (node (ref "USB_TO_UART") (pin "5") (pinfunction "GND_5") (pintype "unspecified"))
    )
    (net (code "14") (name "GPIO0") (class "Default")
      (node (ref "MICROCONTROLLER") (pin "25") (pinfunction "IO0_25") (pintype "unspecified"))
      (node (ref "SW1") (pin "1") (pinfunction "1_1") (pintype "unspecified"))
      (node (ref "U19") (pin "1") (pinfunction "1_1") (pintype "unspecified"))
      (node (ref "U21") (pin "2") (pinfunction "2_2") (pintype "unspecified"))
      (node (ref "U26") (pin "5") (pinfunction "5_5") (pintype "unspecified"))
    )
    (net (code "15") (name "GPS_RX") (class "Default")
      (node (ref "GPS") (pin "21") (pinfunction "RxD1_21") (pintype "unspecified"))
      (node (ref "MICROCONTROLLER") (pin "28") (pinfunction "IO17_28") (pintype "unspecified"))
    )
    (net (code "16") (name "GPS_TX") (class "Default")
      (node (ref "GPS") (pin "20") (pinfunction "TxD1_20") (pintype "unspecified"))
      (node (ref "MICROCONTROLLER") (pin "27") (pinfunction "IO16_27") (pintype "unspecified"))
    )
    (net (code "17") (name "GSM_RX") (class "Default")
      (node (ref "GSM_MODULE_A7670C") (pin "9") (pinfunction "TXD_9") (pintype "input"))
      (node (ref "MICROCONTROLLER") (pin "12") (pinfunction "IO27_12") (pintype "unspecified"))
    )
    (net (code "18") (name "GSM_TX") (class "Default")
      (node (ref "GSM_MODULE_A7670C") (pin "10") (pinfunction "RXD_10") (pintype "input"))
      (node (ref "MICROCONTROLLER") (pin "11") (pinfunction "IO26_11") (pintype "unspecified"))
    )
    (net (code "19") (name "Net-(+5V_to_3.3V_CONVERSION-IN)") (class "Default")
      (node (ref "+5V_to_3.3V_CONVERSION") (pin "3") (pinfunction "IN_3") (pintype "unspecified"))
      (node (ref "U8") (pin "1") (pinfunction "1_1") (pintype "unspecified"))
    )
    (net (code "20") (name "Net-(+5V_to_3.3V_CONVERSION-OUT-Pad2)") (class "Default")
      (node (ref "+5V_to_3.3V_CONVERSION") (pin "2") (pinfunction "OUT_2") (pintype "unspecified"))
      (node (ref "U11") (pin "1") (pinfunction "1_1") (pintype "unspecified"))
    )
    (net (code "21") (name "Net-(+5V_to_3.3V_CONVERSION-OUT-Pad4)") (class "Default")
      (node (ref "+5V_to_3.3V_CONVERSION") (pin "4") (pinfunction "OUT_4") (pintype "unspecified"))
      (node (ref "U9") (pin "1") (pinfunction "1_1") (pintype "unspecified"))
    )
    (net (code "22") (name "Net-(+12V_to_5V_CONV.-VIN)") (class "Default")
      (node (ref "+12V_to_5V_CONV.") (pin "1") (pinfunction "VIN_1") (pintype "unspecified"))
      (node (ref "U2") (pin "1") (pinfunction "1_1") (pintype "unspecified"))
    )
    (net (code "23") (name "Net-(100nF-Pad1)") (class "Default")
      (node (ref "100nF") (pin "1") (pinfunction "1_1") (pintype "input"))
      (node (ref "GSM_MODULE_A7670C") (pin "56") (pinfunction "VBAT_56") (pintype "input"))
    )
    (net (code "24") (name "Net-(1000uf-Pad1)") (class "Default")
      (node (ref "1000uf") (pin "1") (pinfunction "1_1") (pintype "input"))
      (node (ref "GSM_MODULE_A7670C") (pin "57") (pinfunction "VBAT_57") (pintype "input"))
    )
    (net (code "25") (name "Net-(C11-Pad2)") (class "Default")
      (node (ref "C11") (pin "2") (pinfunction "2_2") (pintype "unspecified"))
      (node (ref "R8") (pin "1") (pinfunction "1_1") (pintype "unspecified"))
    )
    (net (code "26") (name "Net-(D1-K)") (class "Default")
      (node (ref "D1") (pin "1") (pinfunction "K_1") (pintype "unspecified"))
      (node (ref "GPS") (pin "22") (pinfunction "V_BCKP_22") (pintype "unspecified"))
      (node (ref "U16") (pin "1") (pinfunction "1_1") (pintype "unspecified"))
    )
    (net (code "27") (name "Net-(GPS-RF_IN)") (class "Default")
      (node (ref "GPS") (pin "11") (pinfunction "RF_IN_11") (pintype "unspecified"))
      (node (ref "L1") (pin "1") (pinfunction "ANT_1") (pintype "unspecified"))
    )
    (net (code "28") (name "Net-(GPS-TIMEPULSE)") (class "Default")
      (node (ref "GPS") (pin "3") (pinfunction "TIMEPULSE_3") (pintype "unspecified"))
      (node (ref "R11") (pin "2") (pinfunction "2_2") (pintype "unspecified"))
    )
    (net (code "29") (name "Net-(GPS1--)") (class "Default")
      (node (ref "GPS1") (pin "2") (pinfunction "-_2") (pintype "unspecified"))
      (node (ref "R11") (pin "1") (pinfunction "1_1") (pintype "unspecified"))
    )
    (net (code "30") (name "Net-(GSM-A)") (class "Default")
      (node (ref "GSM") (pin "1") (pinfunction "A_1") (pintype "unspecified"))
      (node (ref "GSM_MODULE_A7670C") (pin "52") (pinfunction "NETLIGHT_52") (pintype "input"))
    )
    (net (code "31") (name "Net-(GSM-K)") (class "Default")
      (node (ref "GSM") (pin "2") (pinfunction "K_2") (pintype "unspecified"))
      (node (ref "R12") (pin "1") (pinfunction "1_1") (pintype "input"))
    )
    (net (code "32") (name "Net-(GSM_MODULE_A7670C-PWRKEY)") (class "Default")
      (node (ref "GSM_MODULE_A7670C") (pin "1") (pinfunction "PWRKEY_1") (pintype "input"))
      (node (ref "R2") (pin "2") (pinfunction "2_2") (pintype "input"))
    )
    (net (code "33") (name "Net-(GSM_MODULE_A7670C-RESET)") (class "Default")
      (node (ref "GSM_MODULE_A7670C") (pin "16") (pinfunction "RESET_16") (pintype "input"))
      (node (ref "R1") (pin "2") (pinfunction "2_2") (pintype "input"))
    )
    (net (code "34") (name "Net-(GSM_MODULE_A7670C-VBAT-Pad55)") (class "Default")
      (node (ref "GSM_MODULE_A7670C") (pin "55") (pinfunction "VBAT_55") (pintype "input"))
      (node (ref "U28") (pin "1") (pinfunction "1_1") (pintype "unspecified"))
    )
    (net (code "35") (name "Net-(LED-+)") (class "Default")
      (node (ref "LED") (pin "2") (pinfunction "+_2") (pintype "unspecified"))
      (node (ref "R7") (pin "2") (pinfunction "2_2") (pintype "input"))
    )
    (net (code "36") (name "Net-(MICROCONTROLLER-IO2)") (class "Default")
      (node (ref "MICROCONTROLLER") (pin "24") (pinfunction "IO2_24") (pintype "unspecified"))
      (node (ref "R7") (pin "1") (pinfunction "1_1") (pintype "input"))
    )
    (net (code "37") (name "Net-(PWR--)") (class "Default")
      (node (ref "PWR") (pin "1") (pinfunction "-_1") (pintype "unspecified"))
      (node (ref "R9") (pin "2") (pinfunction "2_2") (pintype "input"))
    )
    (net (code "38") (name "Net-(U2-Pad2)") (class "Default")
      (node (ref "U2") (pin "2") (pinfunction "2_2") (pintype "unspecified"))
      (node (ref "U5") (pin "2") (pinfunction "2_2") (pintype "unspecified"))
    )
    (net (code "39") (name "Net-(U7-Pad2)") (class "Default")
      (node (ref "U7") (pin "2") (pinfunction "2_2") (pintype "unspecified"))
      (node (ref "U8") (pin "2") (pinfunction "2_2") (pintype "unspecified"))
    )
    (net (code "40") (name "Net-(U10-Pad2)") (class "Default")
      (node (ref "U10") (pin "2") (pinfunction "2_2") (pintype "unspecified"))
      (node (ref "U9") (pin "2") (pinfunction "2_2") (pintype "unspecified"))
    )
    (net (code "41") (name "Net-(U11-Pad2)") (class "Default")
      (node (ref "U11") (pin "2") (pinfunction "2_2") (pintype "unspecified"))
      (node (ref "U12") (pin "2") (pinfunction "2_2") (pintype "unspecified"))
    )
    (net (code "42") (name "Net-(U17-FB)") (class "Default")
      (node (ref "R4") (pin "2") (pinfunction "2_2") (pintype "input"))
      (node (ref "R5") (pin "2") (pinfunction "2_2") (pintype "input"))
      (node (ref "U17") (pin "4") (pinfunction "FB_4") (pintype "input"))
    )
    (net (code "43") (name "Net-(U17-VIN)") (class "Default")
      (node (ref "1000nf") (pin "1") (pinfunction "1_1") (pintype "input"))
      (node (ref "U17") (pin "1") (pinfunction "VIN_1") (pintype "input"))
      (node (ref "U31") (pin "2") (pinfunction "2_2") (pintype "unspecified"))
    )
    (net (code "44") (name "Net-(U17-VOUT)") (class "Default")
      (node (ref "L3") (pin "2") (pinfunction "2_2") (pintype "input"))
      (node (ref "U17") (pin "2") (pinfunction "VOUT_2") (pintype "input"))
    )
    (net (code "45") (name "Net-(U23-RST#)") (class "Default")
      (node (ref "U23") (pin "9") (pinfunction "RST#_9") (pintype "unspecified"))
      (node (ref "U25") (pin "2") (pinfunction "2_2") (pintype "unspecified"))
    )
    (net (code "46") (name "Net-(U23-VDD)") (class "Default")
      (node (ref "U23") (pin "6") (pinfunction "VDD_6") (pintype "unspecified"))
      (node (ref "U24") (pin "1") (pinfunction "1_1") (pintype "unspecified"))
      (node (ref "U25") (pin "1") (pinfunction "1_1") (pintype "unspecified"))
    )
    (net (code "47") (name "Net-(U24-Pad2)") (class "Default")
      (node (ref "U24") (pin "2") (pinfunction "2_2") (pintype "unspecified"))
      (node (ref "U29") (pin "1") (pinfunction "1_1") (pintype "input"))
    )
    (net (code "48") (name "Net-(USB_TO_UART-SHELL)") (class "Default")
      (node (ref "R8") (pin "2") (pinfunction "2_2") (pintype "unspecified"))
      (node (ref "USB_TO_UART") (pin "6") (pinfunction "SHELL_6") (pintype "unspecified"))
    )
    (net (code "49") (name "SIM_CLK") (class "Default")
      (node (ref "GSM_MODULE_A7670C") (pin "32") (pinfunction "SIM_CLK_32") (pintype "input"))
      (node (ref "SIM_HOLDER") (pin "C3") (pinfunction "CLK_C3") (pintype "unspecified"))
    )
    (net (code "50") (name "SIM_DETECT_SWITCH") (class "Default")
      (node (ref "GSM_MODULE_A7670C") (pin "34") (pinfunction "SIM_DET_34") (pintype "input"))
      (node (ref "SIM_HOLDER") (pin "CD") (pinfunction "CD_CD") (pintype "unspecified"))
    )
    (net (code "51") (name "SIM_HOLDER_VCC") (class "Default")
      (node (ref "GSM_MODULE_A7670C") (pin "30") (pinfunction "SIM_VDD_30") (pintype "input"))
      (node (ref "SIM_HOLDER") (pin "C1") (pinfunction "VCC_C1") (pintype "unspecified"))
    )
    (net (code "52") (name "SIM_IO") (class "Default")
      (node (ref "GSM_MODULE_A7670C") (pin "31") (pinfunction "SIM_DATA_31") (pintype "input"))
      (node (ref "SIM_HOLDER") (pin "C7") (pinfunction "I/O_C7") (pintype "unspecified"))
    )
    (net (code "53") (name "SIM_RST") (class "Default")
      (node (ref "GSM_MODULE_A7670C") (pin "33") (pinfunction "SIM_RST_33") (pintype "input"))
      (node (ref "SIM_HOLDER") (pin "C2") (pinfunction "RST_C2") (pintype "unspecified"))
    )
    (net (code "54") (name "USB_UART_DTR") (class "Default")
      (node (ref "U21") (pin "1") (pinfunction "1_1") (pintype "unspecified"))
      (node (ref "U23") (pin "28") (pinfunction "DTR_28") (pintype "unspecified"))
    )
    (net (code "55") (name "USB_UART_RTS") (class "Default")
      (node (ref "U22") (pin "2") (pinfunction "2_2") (pintype "unspecified"))
      (node (ref "U23") (pin "24") (pinfunction "RTS_24") (pintype "unspecified"))
    )
    (net (code "56") (name "USB_UART_RX") (class "Default")
      (node (ref "MICROCONTROLLER") (pin "34") (pinfunction "RXD0_34") (pintype "unspecified"))
      (node (ref "U23") (pin "26") (pinfunction "TXD_26") (pintype "unspecified"))
      (node (ref "U26") (pin "4") (pinfunction "4_4") (pintype "unspecified"))
    )
    (net (code "57") (name "USB_UART_TX") (class "Default")
      (node (ref "MICROCONTROLLER") (pin "35") (pinfunction "TXD0_35") (pintype "unspecified"))
      (node (ref "U23") (pin "25") (pinfunction "RXD_25") (pintype "unspecified"))
      (node (ref "U26") (pin "3") (pinfunction "3_3") (pintype "unspecified"))
    )
    (net (code "58") (name "VOUT") (class "Default")
      (node (ref "+12V_to_5V_CONV.") (pin "2") (pinfunction "VOUT_2") (pintype "unspecified"))
      (node (ref "L2") (pin "1") (pinfunction "1_1") (pintype "unspecified"))
    )
    (net (code "59") (name "unconnected-(CAN_TRANS-Vref-Pad5)") (class "Default")
      (node (ref "CAN_TRANS") (pin "5") (pinfunction "Vref_5") (pintype "unspecified+no_connect"))
    )
    (net (code "60") (name "unconnected-(GPS-CFG_GPS0{slash}SCK-Pad16)") (class "Default")
      (node (ref "GPS") (pin "16") (pinfunction "CFG_GPS0/SCK_16") (pintype "unspecified+no_connect"))
    )
    (net (code "61") (name "unconnected-(GPS-EXTINT0-Pad4)") (class "Default")
      (node (ref "GPS") (pin "4") (pinfunction "EXTINT0_4") (pintype "unspecified+no_connect"))
    )
    (net (code "62") (name "unconnected-(GPS-MISO{slash}CFG_COM1-Pad15)") (class "Default")
      (node (ref "GPS") (pin "15") (pinfunction "MISO/CFG_COM1_15") (pintype "unspecified+no_connect"))
    )
    (net (code "63") (name "unconnected-(GPS-MOSI{slash}CFG_COM0-Pad14)") (class "Default")
      (node (ref "GPS") (pin "14") (pinfunction "MOSI/CFG_COM0_14") (pintype "unspecified+no_connect"))
    )
    (net (code "64") (name "unconnected-(GPS-Reserved-Pad1)") (class "Default")
      (node (ref "GPS") (pin "1") (pinfunction "Reserved_1") (pintype "unspecified+no_connect"))
    )
    (net (code "65") (name "unconnected-(GPS-Reserved-Pad8)") (class "Default")
      (node (ref "GPS") (pin "8") (pinfunction "Reserved_8") (pintype "unspecified+no_connect"))
    )
    (net (code "66") (name "unconnected-(GPS-Reserved-Pad17)") (class "Default")
      (node (ref "GPS") (pin "17") (pinfunction "Reserved_17") (pintype "unspecified+no_connect"))
    )
    (net (code "67") (name "unconnected-(GPS-SCL2-Pad19)") (class "Default")
      (node (ref "GPS") (pin "19") (pinfunction "SCL2_19") (pintype "unspecified+no_connect"))
    )
    (net (code "68") (name "unconnected-(GPS-SDA2-Pad18)") (class "Default")
      (node (ref "GPS") (pin "18") (pinfunction "SDA2_18") (pintype "unspecified+no_connect"))
    )
    (net (code "69") (name "unconnected-(GPS-SS_N-Pad2)") (class "Default")
      (node (ref "GPS") (pin "2") (pinfunction "SS_N_2") (pintype "unspecified+no_connect"))
    )
    (net (code "70") (name "unconnected-(GPS-USB_DM-Pad5)") (class "Default")
      (node (ref "GPS") (pin "5") (pinfunction "USB_DM_5") (pintype "unspecified+no_connect"))
    )
    (net (code "71") (name "unconnected-(GPS-USB_DP-Pad6)") (class "Default")
      (node (ref "GPS") (pin "6") (pinfunction "USB_DP_6") (pintype "unspecified+no_connect"))
    )
    (net (code "72") (name "unconnected-(GPS-VCC_RF-Pad9)") (class "Default")
      (node (ref "GPS") (pin "9") (pinfunction "VCC_RF_9") (pintype "unspecified+no_connect"))
    )
    (net (code "73") (name "unconnected-(GPS-VDDUSB-Pad7)") (class "Default")
      (node (ref "GPS") (pin "7") (pinfunction "VDDUSB_7") (pintype "unspecified+no_connect"))
    )
    (net (code "74") (name "unconnected-(GSM_MODULE_A7670C-ADC-Pad25)") (class "Default")
      (node (ref "GSM_MODULE_A7670C") (pin "25") (pinfunction "ADC_25") (pintype "input+no_connect"))
    )
    (net (code "75") (name "unconnected-(GSM_MODULE_A7670C-CTS-Pad7)") (class "Default")
      (node (ref "GSM_MODULE_A7670C") (pin "7") (pinfunction "CTS_7") (pintype "input+no_connect"))
    )
    (net (code "76") (name "unconnected-(GSM_MODULE_A7670C-DCD-Pad5)") (class "Default")
      (node (ref "GSM_MODULE_A7670C") (pin "5") (pinfunction "DCD_5") (pintype "input+no_connect"))
    )
    (net (code "77") (name "unconnected-(GSM_MODULE_A7670C-DTR-Pad3)") (class "Default")
      (node (ref "GSM_MODULE_A7670C") (pin "3") (pinfunction "DTR_3") (pintype "input+no_connect"))
    )
    (net (code "78") (name "unconnected-(GSM_MODULE_A7670C-GND-Pad2)") (class "Default")
      (node (ref "GSM_MODULE_A7670C") (pin "2") (pinfunction "GND_2") (pintype "input+no_connect"))
    )
    (net (code "79") (name "unconnected-(GSM_MODULE_A7670C-GND-Pad29)") (class "Default")
      (node (ref "GSM_MODULE_A7670C") (pin "29") (pinfunction "GND_29") (pintype "input+no_connect"))
    )
    (net (code "80") (name "unconnected-(GSM_MODULE_A7670C-GND-Pad39)") (class "Default")
      (node (ref "GSM_MODULE_A7670C") (pin "39") (pinfunction "GND_39") (pintype "input+no_connect"))
    )
    (net (code "81") (name "unconnected-(GSM_MODULE_A7670C-GND-Pad46)") (class "Default")
      (node (ref "GSM_MODULE_A7670C") (pin "46") (pinfunction "GND_46") (pintype "input+no_connect"))
    )
    (net (code "82") (name "unconnected-(GSM_MODULE_A7670C-GND-Pad54)") (class "Default")
      (node (ref "GSM_MODULE_A7670C") (pin "54") (pinfunction "GND_54") (pintype "input+no_connect"))
    )
    (net (code "83") (name "unconnected-(GSM_MODULE_A7670C-GND-Pad58)") (class "Default")
      (node (ref "GSM_MODULE_A7670C") (pin "58") (pinfunction "GND_58") (pintype "input+no_connect"))
    )
    (net (code "84") (name "unconnected-(GSM_MODULE_A7670C-GND-Pad59)") (class "Default")
      (node (ref "GSM_MODULE_A7670C") (pin "59") (pinfunction "GND_59") (pintype "input+no_connect"))
    )
    (net (code "85") (name "unconnected-(GSM_MODULE_A7670C-GND-Pad61)") (class "Default")
      (node (ref "GSM_MODULE_A7670C") (pin "61") (pinfunction "GND_61") (pintype "input+no_connect"))
    )
    (net (code "86") (name "unconnected-(GSM_MODULE_A7670C-GND-Pad62)") (class "Default")
      (node (ref "GSM_MODULE_A7670C") (pin "62") (pinfunction "GND_62") (pintype "input+no_connect"))
    )
    (net (code "87") (name "unconnected-(GSM_MODULE_A7670C-GND-Pad63)") (class "Default")
      (node (ref "GSM_MODULE_A7670C") (pin "63") (pinfunction "GND_63") (pintype "input+no_connect"))
    )
    (net (code "88") (name "unconnected-(GSM_MODULE_A7670C-GND-Pad64)") (class "Default")
      (node (ref "GSM_MODULE_A7670C") (pin "64") (pinfunction "GND_64") (pintype "input+no_connect"))
    )
    (net (code "89") (name "unconnected-(GSM_MODULE_A7670C-GND-Pad65)") (class "Default")
      (node (ref "GSM_MODULE_A7670C") (pin "65") (pinfunction "GND_65") (pintype "input+no_connect"))
    )
    (net (code "90") (name "unconnected-(GSM_MODULE_A7670C-GND-Pad69)") (class "Default")
      (node (ref "GSM_MODULE_A7670C") (pin "69") (pinfunction "GND_69") (pintype "input+no_connect"))
    )
    (net (code "91") (name "unconnected-(GSM_MODULE_A7670C-GND-Pad70)") (class "Default")
      (node (ref "GSM_MODULE_A7670C") (pin "70") (pinfunction "GND_70") (pintype "input+no_connect"))
    )
    (net (code "92") (name "unconnected-(GSM_MODULE_A7670C-GND-Pad71)") (class "Default")
      (node (ref "GSM_MODULE_A7670C") (pin "71") (pinfunction "GND_71") (pintype "input+no_connect"))
    )
    (net (code "93") (name "unconnected-(GSM_MODULE_A7670C-GND-Pad72)") (class "Default")
      (node (ref "GSM_MODULE_A7670C") (pin "72") (pinfunction "GND_72") (pintype "input+no_connect"))
    )
    (net (code "94") (name "unconnected-(GSM_MODULE_A7670C-GND-Pad73)") (class "Default")
      (node (ref "GSM_MODULE_A7670C") (pin "73") (pinfunction "GND_73") (pintype "input+no_connect"))
    )
    (net (code "95") (name "unconnected-(GSM_MODULE_A7670C-GND-Pad74)") (class "Default")
      (node (ref "GSM_MODULE_A7670C") (pin "74") (pinfunction "GND_74") (pintype "input+no_connect"))
    )
    (net (code "96") (name "unconnected-(GSM_MODULE_A7670C-GND-Pad75)") (class "Default")
      (node (ref "GSM_MODULE_A7670C") (pin "75") (pinfunction "GND_75") (pintype "input+no_connect"))
    )
    (net (code "97") (name "unconnected-(GSM_MODULE_A7670C-GND-Pad76)") (class "Default")
      (node (ref "GSM_MODULE_A7670C") (pin "76") (pinfunction "GND_76") (pintype "input+no_connect"))
    )
    (net (code "98") (name "unconnected-(GSM_MODULE_A7670C-GND-Pad77)") (class "Default")
      (node (ref "GSM_MODULE_A7670C") (pin "77") (pinfunction "GND_77") (pintype "input+no_connect"))
    )
    (net (code "99") (name "unconnected-(GSM_MODULE_A7670C-GND-Pad78)") (class "Default")
      (node (ref "GSM_MODULE_A7670C") (pin "78") (pinfunction "GND_78") (pintype "input+no_connect"))
    )
    (net (code "100") (name "unconnected-(GSM_MODULE_A7670C-GND-Pad79)") (class "Default")
      (node (ref "GSM_MODULE_A7670C") (pin "79") (pinfunction "GND_79") (pintype "input+no_connect"))
    )
    (net (code "101") (name "unconnected-(GSM_MODULE_A7670C-GND-Pad80)") (class "Default")
      (node (ref "GSM_MODULE_A7670C") (pin "80") (pinfunction "GND_80") (pintype "input+no_connect"))
    )
    (net (code "102") (name "unconnected-(GSM_MODULE_A7670C-GND-Pad81)") (class "Default")
      (node (ref "GSM_MODULE_A7670C") (pin "81") (pinfunction "GND_81") (pintype "input+no_connect"))
    )
    (net (code "103") (name "unconnected-(GSM_MODULE_A7670C-GND-Pad82)") (class "Default")
      (node (ref "GSM_MODULE_A7670C") (pin "82") (pinfunction "GND_82") (pintype "input+no_connect"))
    )
    (net (code "104") (name "unconnected-(GSM_MODULE_A7670C-GND-Pad83)") (class "Default")
      (node (ref "GSM_MODULE_A7670C") (pin "83") (pinfunction "GND_83") (pintype "input+no_connect"))
    )
    (net (code "105") (name "unconnected-(GSM_MODULE_A7670C-GND-Pad84)") (class "Default")
      (node (ref "GSM_MODULE_A7670C") (pin "84") (pinfunction "GND_84") (pintype "input+no_connect"))
    )
    (net (code "106") (name "unconnected-(GSM_MODULE_A7670C-GND-Pad85)") (class "Default")
      (node (ref "GSM_MODULE_A7670C") (pin "85") (pinfunction "GND_85") (pintype "input+no_connect"))
    )
    (net (code "107") (name "unconnected-(GSM_MODULE_A7670C-GND-Pad86)") (class "Default")
      (node (ref "GSM_MODULE_A7670C") (pin "86") (pinfunction "GND_86") (pintype "input+no_connect"))
    )
    (net (code "108") (name "unconnected-(GSM_MODULE_A7670C-GND-Pad87)") (class "Default")
      (node (ref "GSM_MODULE_A7670C") (pin "87") (pinfunction "GND_87") (pintype "input+no_connect"))
    )
    (net (code "109") (name "unconnected-(GSM_MODULE_A7670C-GND-Pad88)") (class "Default")
      (node (ref "GSM_MODULE_A7670C") (pin "88") (pinfunction "GND_88") (pintype "input+no_connect"))
    )
    (net (code "110") (name "unconnected-(GSM_MODULE_A7670C-GPIO1-Pad19)") (class "Default")
      (node (ref "GSM_MODULE_A7670C") (pin "19") (pinfunction "GPIO1_19") (pintype "input+no_connect"))
    )
    (net (code "111") (name "unconnected-(GSM_MODULE_A7670C-GPIO2-Pad20)") (class "Default")
      (node (ref "GSM_MODULE_A7670C") (pin "20") (pinfunction "GPIO2_20") (pintype "input+no_connect"))
    )
    (net (code "112") (name "unconnected-(GSM_MODULE_A7670C-GPIO3-Pad21)") (class "Default")
      (node (ref "GSM_MODULE_A7670C") (pin "21") (pinfunction "GPIO3_21") (pintype "input+no_connect"))
    )
    (net (code "113") (name "unconnected-(GSM_MODULE_A7670C-GPIO4(UART3_RX)-Pad49)") (class "Default")
      (node (ref "GSM_MODULE_A7670C") (pin "49") (pinfunction "GPIO4(UART3_RX)_49") (pintype "input+no_connect"))
    )
    (net (code "114") (name "unconnected-(GSM_MODULE_A7670C-GPIO5(UART3_TX)-Pad50)") (class "Default")
      (node (ref "GSM_MODULE_A7670C") (pin "50") (pinfunction "GPIO5(UART3_TX)_50") (pintype "input+no_connect"))
    )
    (net (code "115") (name "unconnected-(GSM_MODULE_A7670C-GPIO9-Pad48)") (class "Default")
      (node (ref "GSM_MODULE_A7670C") (pin "48") (pinfunction "GPIO9_48") (pintype "input+no_connect"))
    )
    (net (code "116") (name "unconnected-(GSM_MODULE_A7670C-GPIO10-Pad67)") (class "Default")
      (node (ref "GSM_MODULE_A7670C") (pin "67") (pinfunction "GPIO10_67") (pintype "input+no_connect"))
    )
    (net (code "117") (name "unconnected-(GSM_MODULE_A7670C-GPIO11-Pad68)") (class "Default")
      (node (ref "GSM_MODULE_A7670C") (pin "68") (pinfunction "GPIO11_68") (pintype "input+no_connect"))
    )
    (net (code "118") (name "unconnected-(GSM_MODULE_A7670C-I2C_SCL-Pad38)") (class "Default")
      (node (ref "GSM_MODULE_A7670C") (pin "38") (pinfunction "I2C_SCL_38") (pintype "input+no_connect"))
    )
    (net (code "119") (name "unconnected-(GSM_MODULE_A7670C-I2C_SDA-Pad37)") (class "Default")
      (node (ref "GSM_MODULE_A7670C") (pin "37") (pinfunction "I2C_SDA_37") (pintype "input+no_connect"))
    )
    (net (code "120") (name "unconnected-(GSM_MODULE_A7670C-NC-Pad26)") (class "Default")
      (node (ref "GSM_MODULE_A7670C") (pin "26") (pinfunction "NC_26") (pintype "input+no_connect"))
    )
    (net (code "121") (name "unconnected-(GSM_MODULE_A7670C-NC-Pad35)") (class "Default")
      (node (ref "GSM_MODULE_A7670C") (pin "35") (pinfunction "NC_35") (pintype "input+no_connect"))
    )
    (net (code "122") (name "unconnected-(GSM_MODULE_A7670C-NC-Pad36)") (class "Default")
      (node (ref "GSM_MODULE_A7670C") (pin "36") (pinfunction "NC_36") (pintype "input+no_connect"))
    )
    (net (code "123") (name "unconnected-(GSM_MODULE_A7670C-NC-Pad40)") (class "Default")
      (node (ref "GSM_MODULE_A7670C") (pin "40") (pinfunction "NC_40") (pintype "input+no_connect"))
    )
    (net (code "124") (name "unconnected-(GSM_MODULE_A7670C-NC-Pad41)") (class "Default")
      (node (ref "GSM_MODULE_A7670C") (pin "41") (pinfunction "NC_41") (pintype "input+no_connect"))
    )
    (net (code "125") (name "unconnected-(GSM_MODULE_A7670C-NC-Pad42)") (class "Default")
      (node (ref "GSM_MODULE_A7670C") (pin "42") (pinfunction "NC_42") (pintype "input+no_connect"))
    )
    (net (code "126") (name "unconnected-(GSM_MODULE_A7670C-NC-Pad43)") (class "Default")
      (node (ref "GSM_MODULE_A7670C") (pin "43") (pinfunction "NC_43") (pintype "input+no_connect"))
    )
    (net (code "127") (name "unconnected-(GSM_MODULE_A7670C-NC-Pad44)") (class "Default")
      (node (ref "GSM_MODULE_A7670C") (pin "44") (pinfunction "NC_44") (pintype "input+no_connect"))
    )
    (net (code "128") (name "unconnected-(GSM_MODULE_A7670C-NC-Pad47)") (class "Default")
      (node (ref "GSM_MODULE_A7670C") (pin "47") (pinfunction "NC_47") (pintype "input+no_connect"))
    )
    (net (code "129") (name "unconnected-(GSM_MODULE_A7670C-NC-Pad51)") (class "Default")
      (node (ref "GSM_MODULE_A7670C") (pin "51") (pinfunction "NC_51") (pintype "input+no_connect"))
    )
    (net (code "130") (name "unconnected-(GSM_MODULE_A7670C-NC-Pad53)") (class "Default")
      (node (ref "GSM_MODULE_A7670C") (pin "53") (pinfunction "NC_53") (pintype "input+no_connect"))
    )
    (net (code "131") (name "unconnected-(GSM_MODULE_A7670C-PCM_CLK-Pad11)") (class "Default")
      (node (ref "GSM_MODULE_A7670C") (pin "11") (pinfunction "PCM_CLK_11") (pintype "input+no_connect"))
    )
    (net (code "132") (name "unconnected-(GSM_MODULE_A7670C-PCM_DIN-Pad13)") (class "Default")
      (node (ref "GSM_MODULE_A7670C") (pin "13") (pinfunction "PCM_DIN_13") (pintype "input+no_connect"))
    )
    (net (code "133") (name "unconnected-(GSM_MODULE_A7670C-PCM_OUT-Pad14)") (class "Default")
      (node (ref "GSM_MODULE_A7670C") (pin "14") (pinfunction "PCM_OUT_14") (pintype "input+no_connect"))
    )
    (net (code "134") (name "unconnected-(GSM_MODULE_A7670C-PCM_SYNC-Pad12)") (class "Default")
      (node (ref "GSM_MODULE_A7670C") (pin "12") (pinfunction "PCM_SYNC_12") (pintype "input+no_connect"))
    )
    (net (code "135") (name "unconnected-(GSM_MODULE_A7670C-RF_ANT-Pad60)") (class "Default")
      (node (ref "GSM_MODULE_A7670C") (pin "60") (pinfunction "RF_ANT_60") (pintype "input+no_connect"))
    )
    (net (code "136") (name "unconnected-(GSM_MODULE_A7670C-RI-Pad4)") (class "Default")
      (node (ref "GSM_MODULE_A7670C") (pin "4") (pinfunction "RI_4") (pintype "input+no_connect"))
    )
    (net (code "137") (name "unconnected-(GSM_MODULE_A7670C-RTS-Pad8)") (class "Default")
      (node (ref "GSM_MODULE_A7670C") (pin "8") (pinfunction "RTS_8") (pintype "input+no_connect"))
    )
    (net (code "138") (name "unconnected-(GSM_MODULE_A7670C-STATUS-Pad66)") (class "Default")
      (node (ref "GSM_MODULE_A7670C") (pin "66") (pinfunction "STATUS_66") (pintype "input+no_connect"))
    )
    (net (code "139") (name "unconnected-(GSM_MODULE_A7670C-UART_LOG_RX-Pad22)") (class "Default")
      (node (ref "GSM_MODULE_A7670C") (pin "22") (pinfunction "UART_LOG_RX_22") (pintype "input+no_connect"))
    )
    (net (code "140") (name "unconnected-(GSM_MODULE_A7670C-UART_LOG_TX-Pad23)") (class "Default")
      (node (ref "GSM_MODULE_A7670C") (pin "23") (pinfunction "UART_LOG_TX_23") (pintype "input+no_connect"))
    )
    (net (code "141") (name "unconnected-(GSM_MODULE_A7670C-USB_BOOT--Pad6)") (class "Default")
      (node (ref "GSM_MODULE_A7670C") (pin "6") (pinfunction "USB_BOOT-_6") (pintype "input+no_connect"))
    )
    (net (code "142") (name "unconnected-(GSM_MODULE_A7670C-USB_DM-Pad28)") (class "Default")
      (node (ref "GSM_MODULE_A7670C") (pin "28") (pinfunction "USB_DM_28") (pintype "input+no_connect"))
    )
    (net (code "143") (name "unconnected-(GSM_MODULE_A7670C-USB_DP-Pad27)") (class "Default")
      (node (ref "GSM_MODULE_A7670C") (pin "27") (pinfunction "USB_DP_27") (pintype "input+no_connect"))
    )
    (net (code "144") (name "unconnected-(GSM_MODULE_A7670C-VBUS-Pad24)") (class "Default")
      (node (ref "GSM_MODULE_A7670C") (pin "24") (pinfunction "VBUS_24") (pintype "input+no_connect"))
    )
    (net (code "145") (name "unconnected-(GSM_MODULE_A7670C-VDD_1V8-Pad15)") (class "Default")
      (node (ref "GSM_MODULE_A7670C") (pin "15") (pinfunction "VDD_1V8_15") (pintype "input+no_connect"))
    )
    (net (code "146") (name "unconnected-(MICROCONTROLLER-CLK-Pad20)") (class "Default")
      (node (ref "MICROCONTROLLER") (pin "20") (pinfunction "CLK_20") (pintype "unspecified+no_connect"))
    )
    (net (code "147") (name "unconnected-(MICROCONTROLLER-CMD-Pad19)") (class "Default")
      (node (ref "MICROCONTROLLER") (pin "19") (pinfunction "CMD_19") (pintype "unspecified+no_connect"))
    )
    (net (code "148") (name "unconnected-(MICROCONTROLLER-IO12-Pad14)") (class "Default")
      (node (ref "MICROCONTROLLER") (pin "14") (pinfunction "IO12_14") (pintype "unspecified+no_connect"))
    )
    (net (code "149") (name "unconnected-(MICROCONTROLLER-IO13-Pad16)") (class "Default")
      (node (ref "MICROCONTROLLER") (pin "16") (pinfunction "IO13_16") (pintype "unspecified+no_connect"))
    )
    (net (code "150") (name "unconnected-(MICROCONTROLLER-IO14-Pad13)") (class "Default")
      (node (ref "MICROCONTROLLER") (pin "13") (pinfunction "IO14_13") (pintype "unspecified+no_connect"))
    )
    (net (code "151") (name "unconnected-(MICROCONTROLLER-IO15-Pad23)") (class "Default")
      (node (ref "MICROCONTROLLER") (pin "23") (pinfunction "IO15_23") (pintype "unspecified+no_connect"))
    )
    (net (code "152") (name "unconnected-(MICROCONTROLLER-IO18-Pad30)") (class "Default")
      (node (ref "MICROCONTROLLER") (pin "30") (pinfunction "IO18_30") (pintype "unspecified+no_connect"))
    )
    (net (code "153") (name "unconnected-(MICROCONTROLLER-IO19-Pad31)") (class "Default")
      (node (ref "MICROCONTROLLER") (pin "31") (pinfunction "IO19_31") (pintype "unspecified+no_connect"))
    )
    (net (code "154") (name "unconnected-(MICROCONTROLLER-IO21-Pad33)") (class "Default")
      (node (ref "MICROCONTROLLER") (pin "33") (pinfunction "IO21_33") (pintype "unspecified+no_connect"))
    )
    (net (code "155") (name "unconnected-(MICROCONTROLLER-IO22-Pad36)") (class "Default")
      (node (ref "MICROCONTROLLER") (pin "36") (pinfunction "IO22_36") (pintype "unspecified+no_connect"))
    )
    (net (code "156") (name "unconnected-(MICROCONTROLLER-IO23-Pad37)") (class "Default")
      (node (ref "MICROCONTROLLER") (pin "37") (pinfunction "IO23_37") (pintype "unspecified+no_connect"))
    )
    (net (code "157") (name "unconnected-(MICROCONTROLLER-IO25-Pad10)") (class "Default")
      (node (ref "MICROCONTROLLER") (pin "10") (pinfunction "IO25_10") (pintype "unspecified+no_connect"))
    )
    (net (code "158") (name "unconnected-(MICROCONTROLLER-IO32-Pad8)") (class "Default")
      (node (ref "MICROCONTROLLER") (pin "8") (pinfunction "IO32_8") (pintype "unspecified+no_connect"))
    )
    (net (code "159") (name "unconnected-(MICROCONTROLLER-IO33-Pad9)") (class "Default")
      (node (ref "MICROCONTROLLER") (pin "9") (pinfunction "IO33_9") (pintype "unspecified+no_connect"))
    )
    (net (code "160") (name "unconnected-(MICROCONTROLLER-IO34-Pad6)") (class "Default")
      (node (ref "MICROCONTROLLER") (pin "6") (pinfunction "IO34_6") (pintype "unspecified+no_connect"))
    )
    (net (code "161") (name "unconnected-(MICROCONTROLLER-IO35-Pad7)") (class "Default")
      (node (ref "MICROCONTROLLER") (pin "7") (pinfunction "IO35_7") (pintype "unspecified+no_connect"))
    )
    (net (code "162") (name "unconnected-(MICROCONTROLLER-NC-Pad32)") (class "Default")
      (node (ref "MICROCONTROLLER") (pin "32") (pinfunction "NC_32") (pintype "unspecified+no_connect"))
    )
    (net (code "163") (name "unconnected-(MICROCONTROLLER-SD0-Pad21)") (class "Default")
      (node (ref "MICROCONTROLLER") (pin "21") (pinfunction "SD0_21") (pintype "unspecified+no_connect"))
    )
    (net (code "164") (name "unconnected-(MICROCONTROLLER-SD1-Pad22)") (class "Default")
      (node (ref "MICROCONTROLLER") (pin "22") (pinfunction "SD1_22") (pintype "unspecified+no_connect"))
    )
    (net (code "165") (name "unconnected-(MICROCONTROLLER-SD2-Pad17)") (class "Default")
      (node (ref "MICROCONTROLLER") (pin "17") (pinfunction "SD2_17") (pintype "unspecified+no_connect"))
    )
    (net (code "166") (name "unconnected-(MICROCONTROLLER-SD3-Pad18)") (class "Default")
      (node (ref "MICROCONTROLLER") (pin "18") (pinfunction "SD3_18") (pintype "unspecified+no_connect"))
    )
    (net (code "167") (name "unconnected-(MICROCONTROLLER-SENSOR_VN-Pad5)") (class "Default")
      (node (ref "MICROCONTROLLER") (pin "5") (pinfunction "SENSOR_VN_5") (pintype "unspecified+no_connect"))
    )
    (net (code "168") (name "unconnected-(MICROCONTROLLER-SENSOR_VP-Pad4)") (class "Default")
      (node (ref "MICROCONTROLLER") (pin "4") (pinfunction "SENSOR_VP_4") (pintype "unspecified+no_connect"))
    )
    (net (code "169") (name "unconnected-(SIM_HOLDER-GND-PadC5)") (class "Default")
      (node (ref "SIM_HOLDER") (pin "C5") (pinfunction "GND_C5") (pintype "unspecified+no_connect"))
    )
    (net (code "170") (name "unconnected-(SIM_HOLDER-VPP-PadC6)") (class "Default")
      (node (ref "SIM_HOLDER") (pin "C6") (pinfunction "VPP_C6") (pintype "unspecified+no_connect"))
    )
    (net (code "171") (name "unconnected-(U23-CTS-Pad23)") (class "Default")
      (node (ref "U23") (pin "23") (pinfunction "CTS_23") (pintype "unspecified+no_connect"))
    )
    (net (code "172") (name "unconnected-(U23-DCD-Pad1)") (class "Default")
      (node (ref "U23") (pin "1") (pinfunction "DCD_1") (pintype "unspecified+no_connect"))
    )
    (net (code "173") (name "unconnected-(U23-DSR-Pad27)") (class "Default")
      (node (ref "U23") (pin "27") (pinfunction "DSR_27") (pintype "unspecified+no_connect"))
    )
    (net (code "174") (name "unconnected-(U23-NC-Pad10)") (class "Default")
      (node (ref "U23") (pin "10") (pinfunction "NC_10") (pintype "unspecified+no_connect"))
    )
    (net (code "175") (name "unconnected-(U23-NC-Pad13)") (class "Default")
      (node (ref "U23") (pin "13") (pinfunction "NC_13") (pintype "unspecified+no_connect"))
    )
    (net (code "176") (name "unconnected-(U23-NC-Pad14)") (class "Default")
      (node (ref "U23") (pin "14") (pinfunction "NC_14") (pintype "unspecified+no_connect"))
    )
    (net (code "177") (name "unconnected-(U23-NC-Pad15)") (class "Default")
      (node (ref "U23") (pin "15") (pinfunction "NC_15") (pintype "unspecified+no_connect"))
    )
    (net (code "178") (name "unconnected-(U23-NC-Pad16)") (class "Default")
      (node (ref "U23") (pin "16") (pinfunction "NC_16") (pintype "unspecified+no_connect"))
    )
    (net (code "179") (name "unconnected-(U23-NC-Pad17)") (class "Default")
      (node (ref "U23") (pin "17") (pinfunction "NC_17") (pintype "unspecified+no_connect"))
    )
    (net (code "180") (name "unconnected-(U23-NC-Pad18)") (class "Default")
      (node (ref "U23") (pin "18") (pinfunction "NC_18") (pintype "unspecified+no_connect"))
    )
    (net (code "181") (name "unconnected-(U23-NC-Pad19)") (class "Default")
      (node (ref "U23") (pin "19") (pinfunction "NC_19") (pintype "unspecified+no_connect"))
    )
    (net (code "182") (name "unconnected-(U23-NC-Pad20)") (class "Default")
      (node (ref "U23") (pin "20") (pinfunction "NC_20") (pintype "unspecified+no_connect"))
    )
    (net (code "183") (name "unconnected-(U23-NC-Pad21)") (class "Default")
      (node (ref "U23") (pin "21") (pinfunction "NC_21") (pintype "unspecified+no_connect"))
    )
    (net (code "184") (name "unconnected-(U23-NC-Pad22)") (class "Default")
      (node (ref "U23") (pin "22") (pinfunction "NC_22") (pintype "unspecified+no_connect"))
    )
    (net (code "185") (name "unconnected-(U23-RI-Pad2)") (class "Default")
      (node (ref "U23") (pin "2") (pinfunction "RI_2") (pintype "unspecified+no_connect"))
    )
    (net (code "186") (name "unconnected-(U23-SUSPEND#-Pad11)") (class "Default")
      (node (ref "U23") (pin "11") (pinfunction "SUSPEND#_11") (pintype "unspecified+no_connect"))
    )
    (net (code "187") (name "unconnected-(U23-SUSPEND-Pad12)") (class "Default")
      (node (ref "U23") (pin "12") (pinfunction "SUSPEND_12") (pintype "unspecified+no_connect"))
    )
    (net (code "188") (name "unconnected-(U30-Pad1)") (class "Default")
      (node (ref "U30") (pin "1") (pinfunction "1_1") (pintype "unspecified+no_connect"))
    )
    (net (code "189") (name "unconnected-(U30-Pad2)") (class "Default")
      (node (ref "U30") (pin "2") (pinfunction "2_2") (pintype "unspecified+no_connect"))
    )
    (net (code "190") (name "unconnected-(U30-Pad3)") (class "Default")
      (node (ref "U30") (pin "3") (pinfunction "3_3") (pintype "unspecified+no_connect"))
    )
    (net (code "191") (name "unconnected-(U30-Pad7)") (class "Default")
      (node (ref "U30") (pin "7") (pinfunction "7_7") (pintype "unspecified+no_connect"))
    )
    (net (code "192") (name "unconnected-(U30-Pad8)") (class "Default")
      (node (ref "U30") (pin "8") (pinfunction "8_8") (pintype "unspecified+no_connect"))
    )
    (net (code "193") (name "unconnected-(U30-Pad9)") (class "Default")
      (node (ref "U30") (pin "9") (pinfunction "9_9") (pintype "unspecified+no_connect"))
    )
    (net (code "194") (name "unconnected-(U30-Pad10)") (class "Default")
      (node (ref "U30") (pin "10") (pinfunction "10_10") (pintype "unspecified+no_connect"))
    )
    (net (code "195") (name "unconnected-(U30-Pad11)") (class "Default")
      (node (ref "U30") (pin "11") (pinfunction "11_11") (pintype "unspecified+no_connect"))
    )
    (net (code "196") (name "unconnected-(U30-Pad12)") (class "Default")
      (node (ref "U30") (pin "12") (pinfunction "12_12") (pintype "unspecified+no_connect"))
    )
    (net (code "197") (name "unconnected-(U30-Pad13)") (class "Default")
      (node (ref "U30") (pin "13") (pinfunction "13_13") (pintype "unspecified+no_connect"))
    )
    (net (code "198") (name "unconnected-(U30-Pad15)") (class "Default")
      (node (ref "U30") (pin "15") (pinfunction "15_15") (pintype "unspecified+no_connect"))
    )
    (net (code "199") (name "unconnected-(USB_TO_UART-ID-Pad4)") (class "Default")
      (node (ref "USB_TO_UART") (pin "4") (pinfunction "ID_4") (pintype "unspecified+no_connect"))
    )
  )
)
